# PART1.net
KiCad netlist of a schematic drawn in Altium Designer
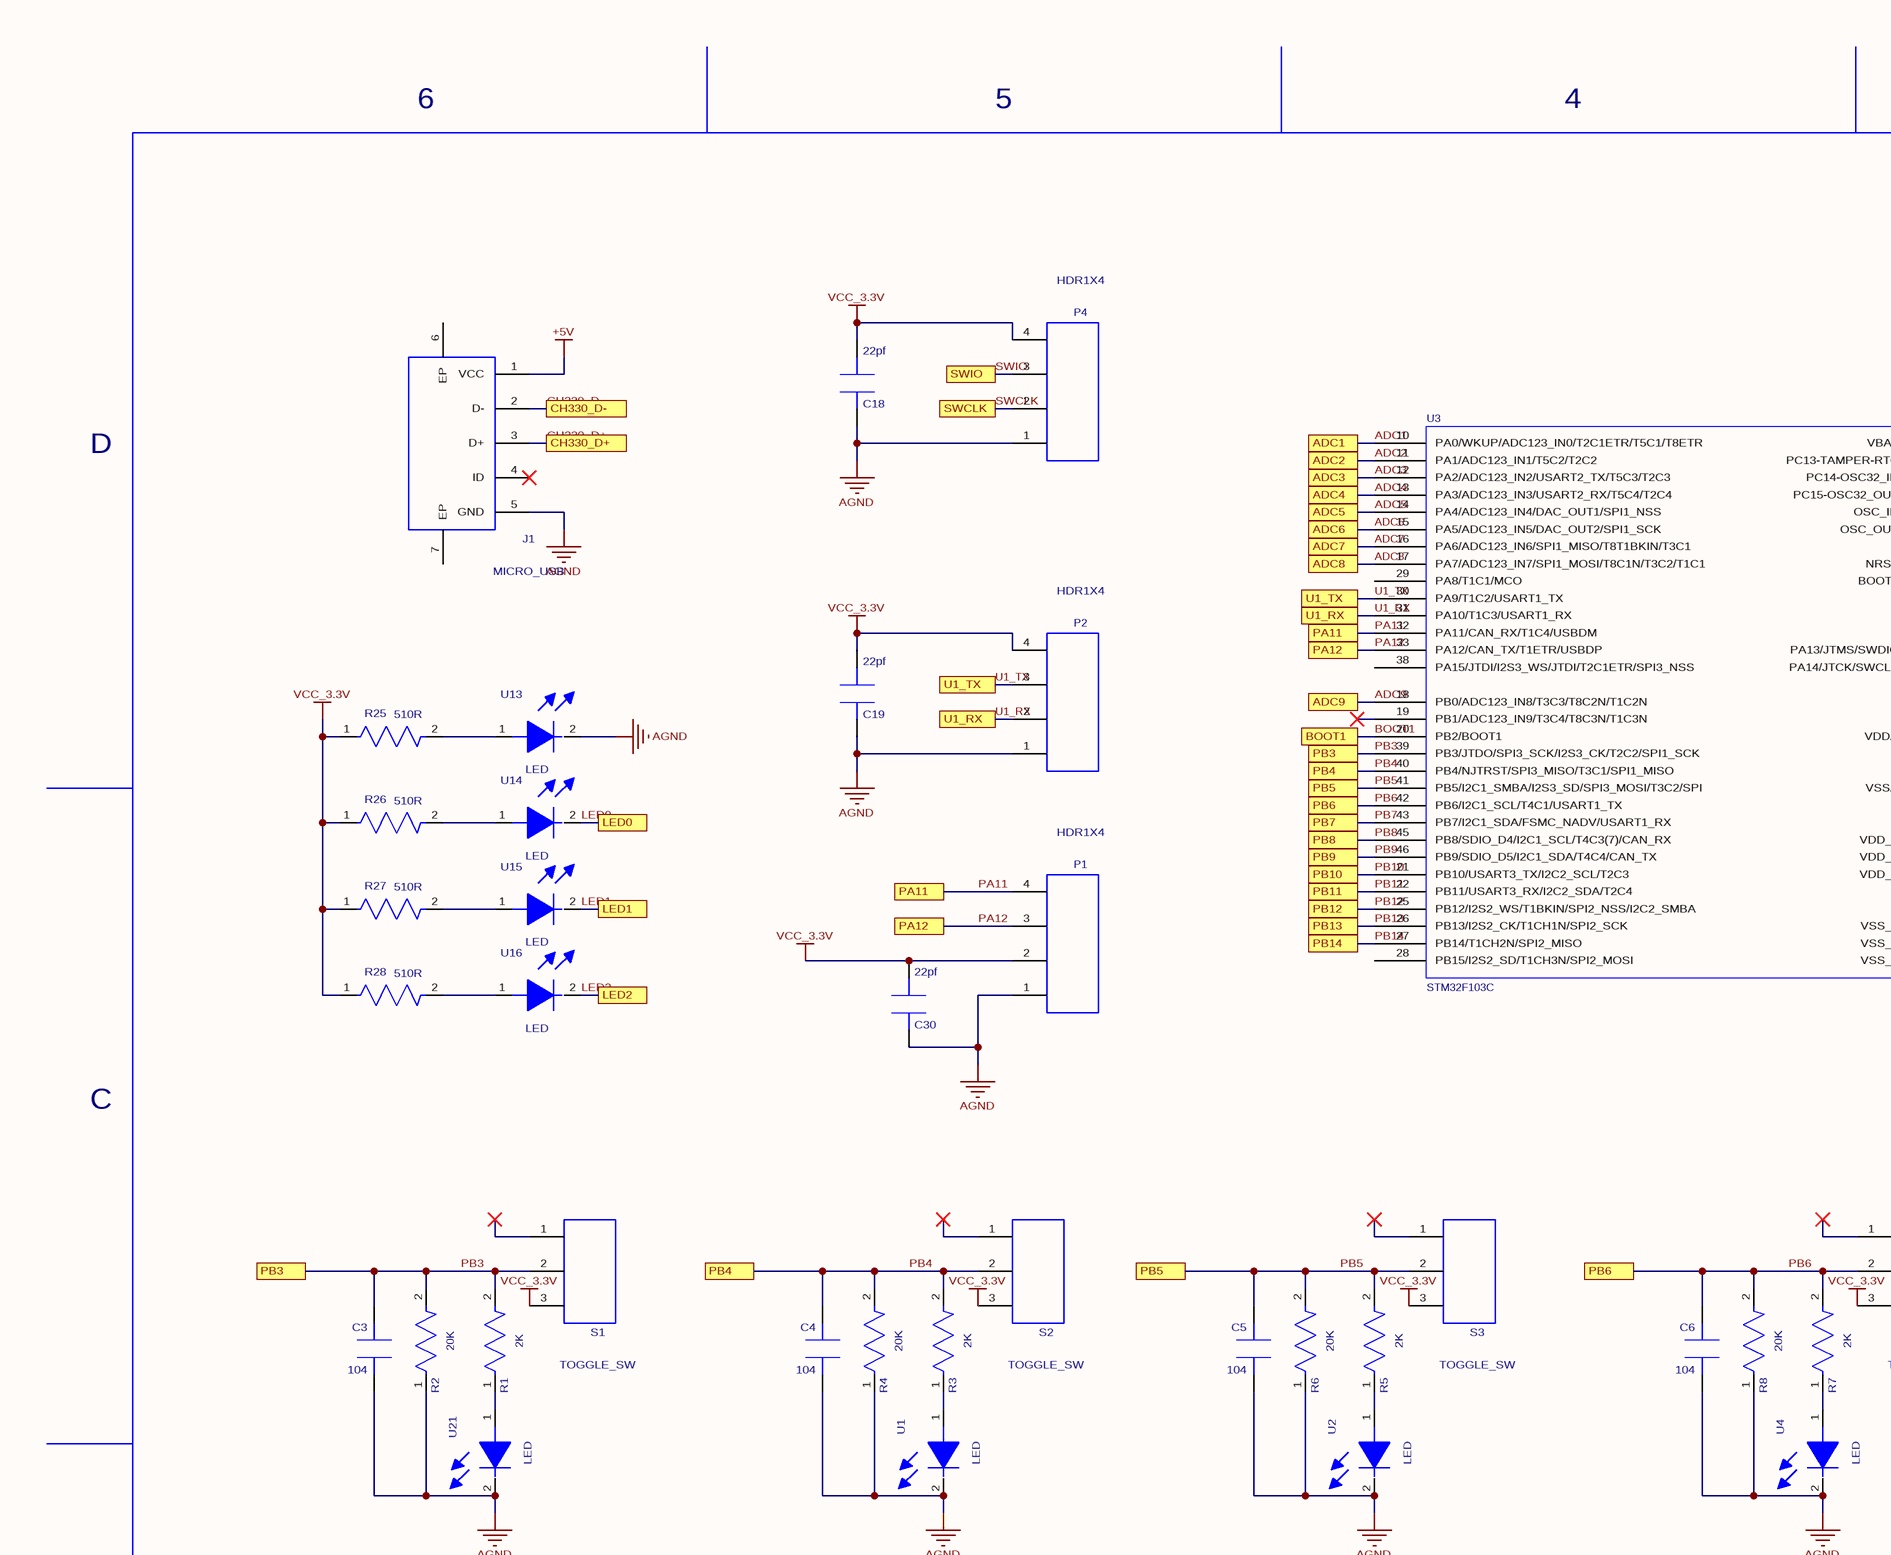
[diagram p0: PART1.SchDoc, top left]
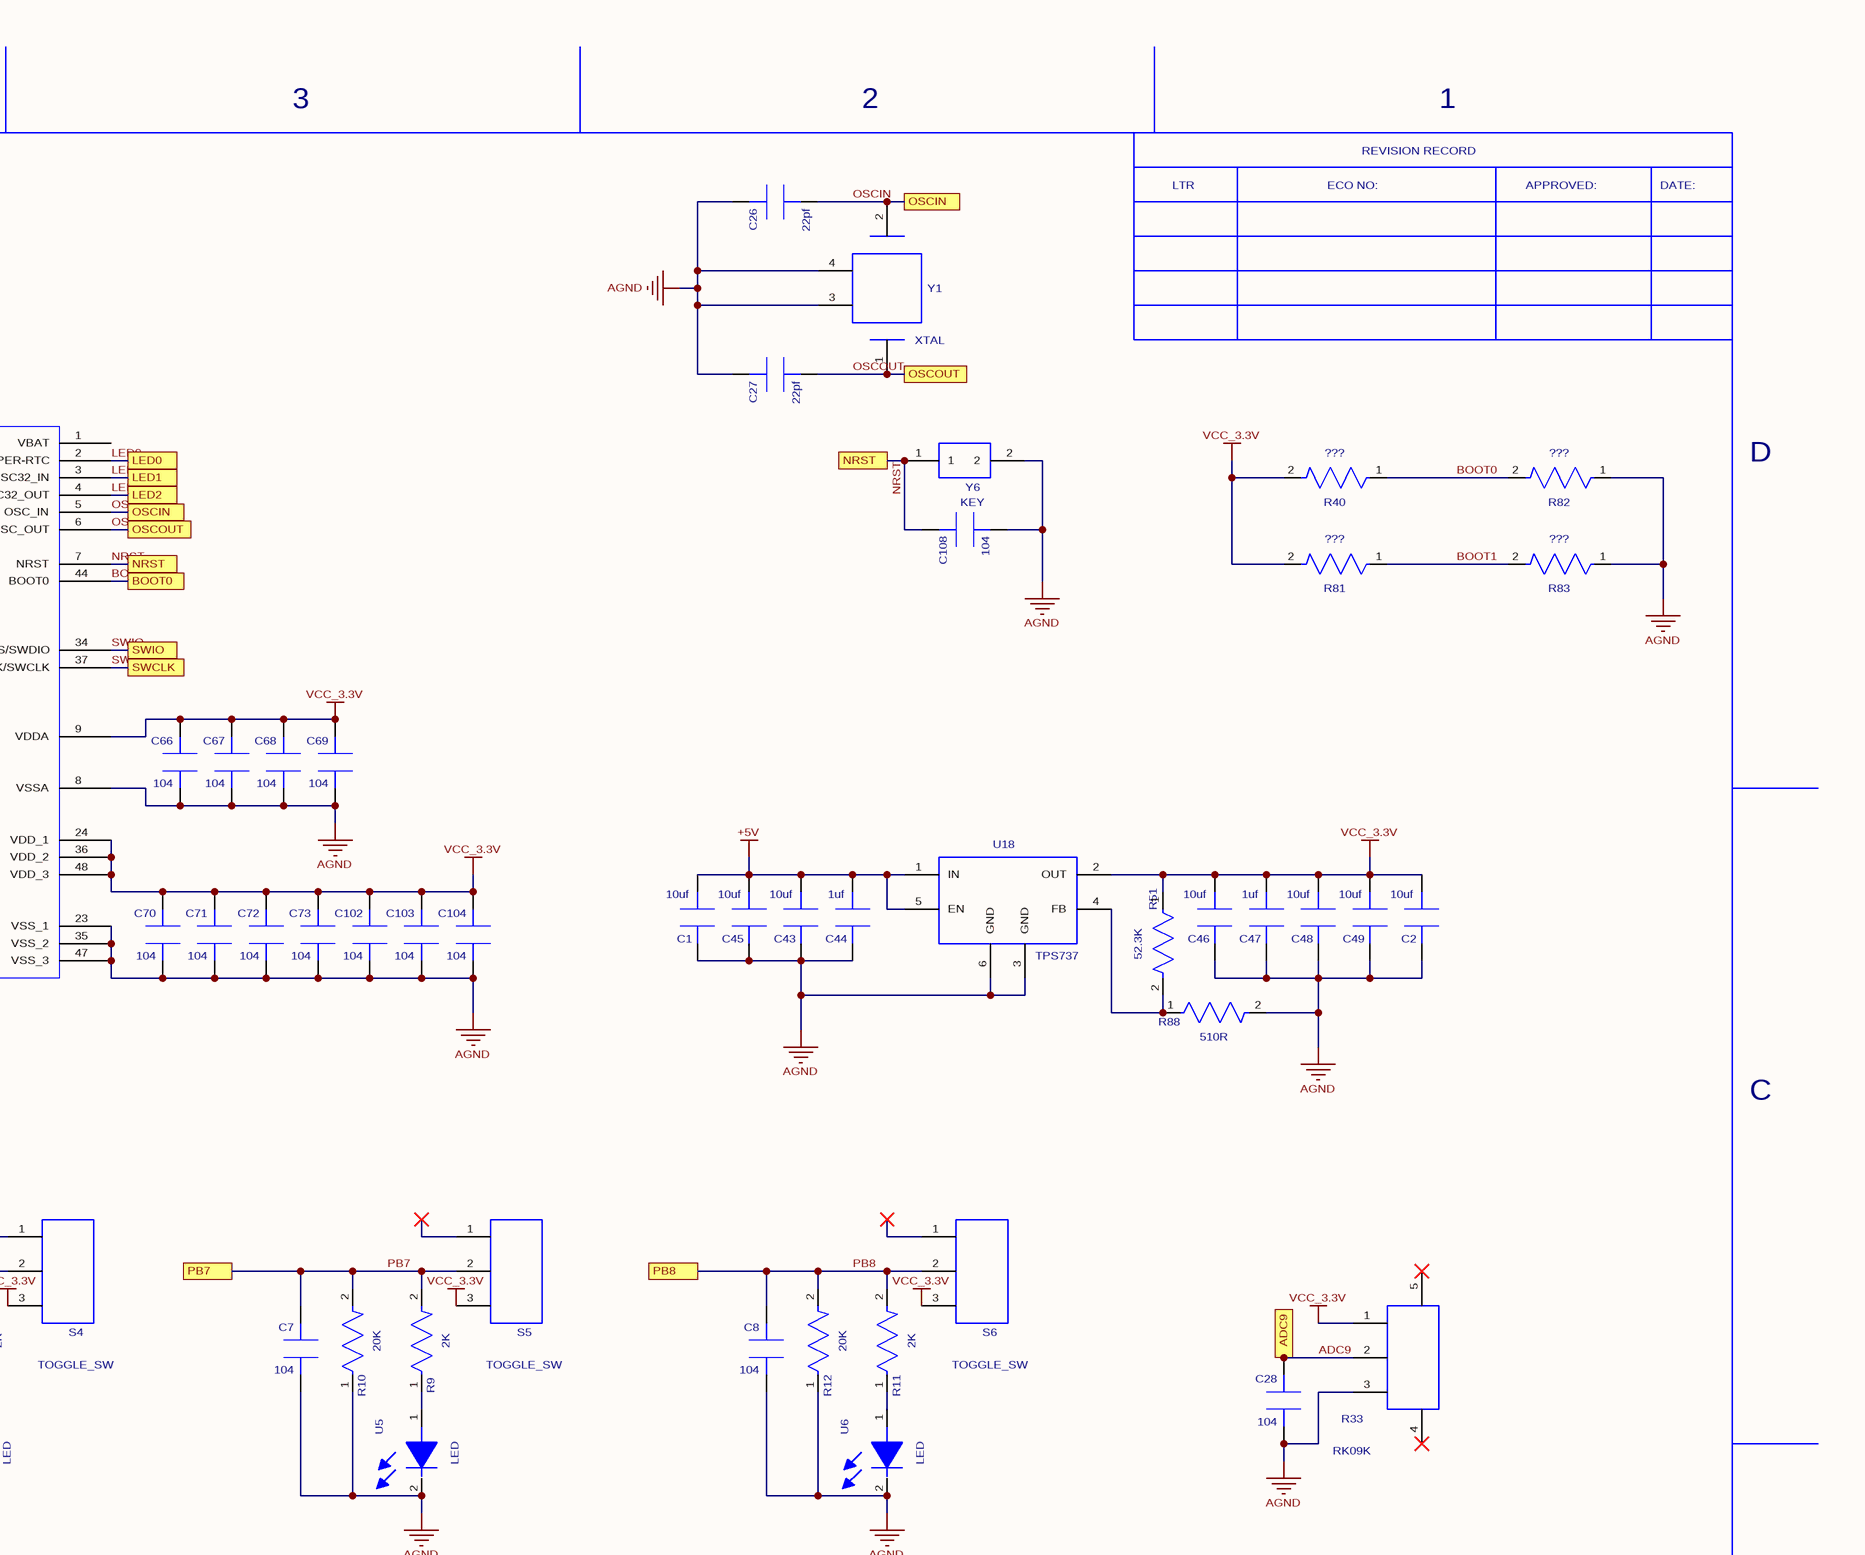
[diagram p1: PART1.SchDoc, top right]
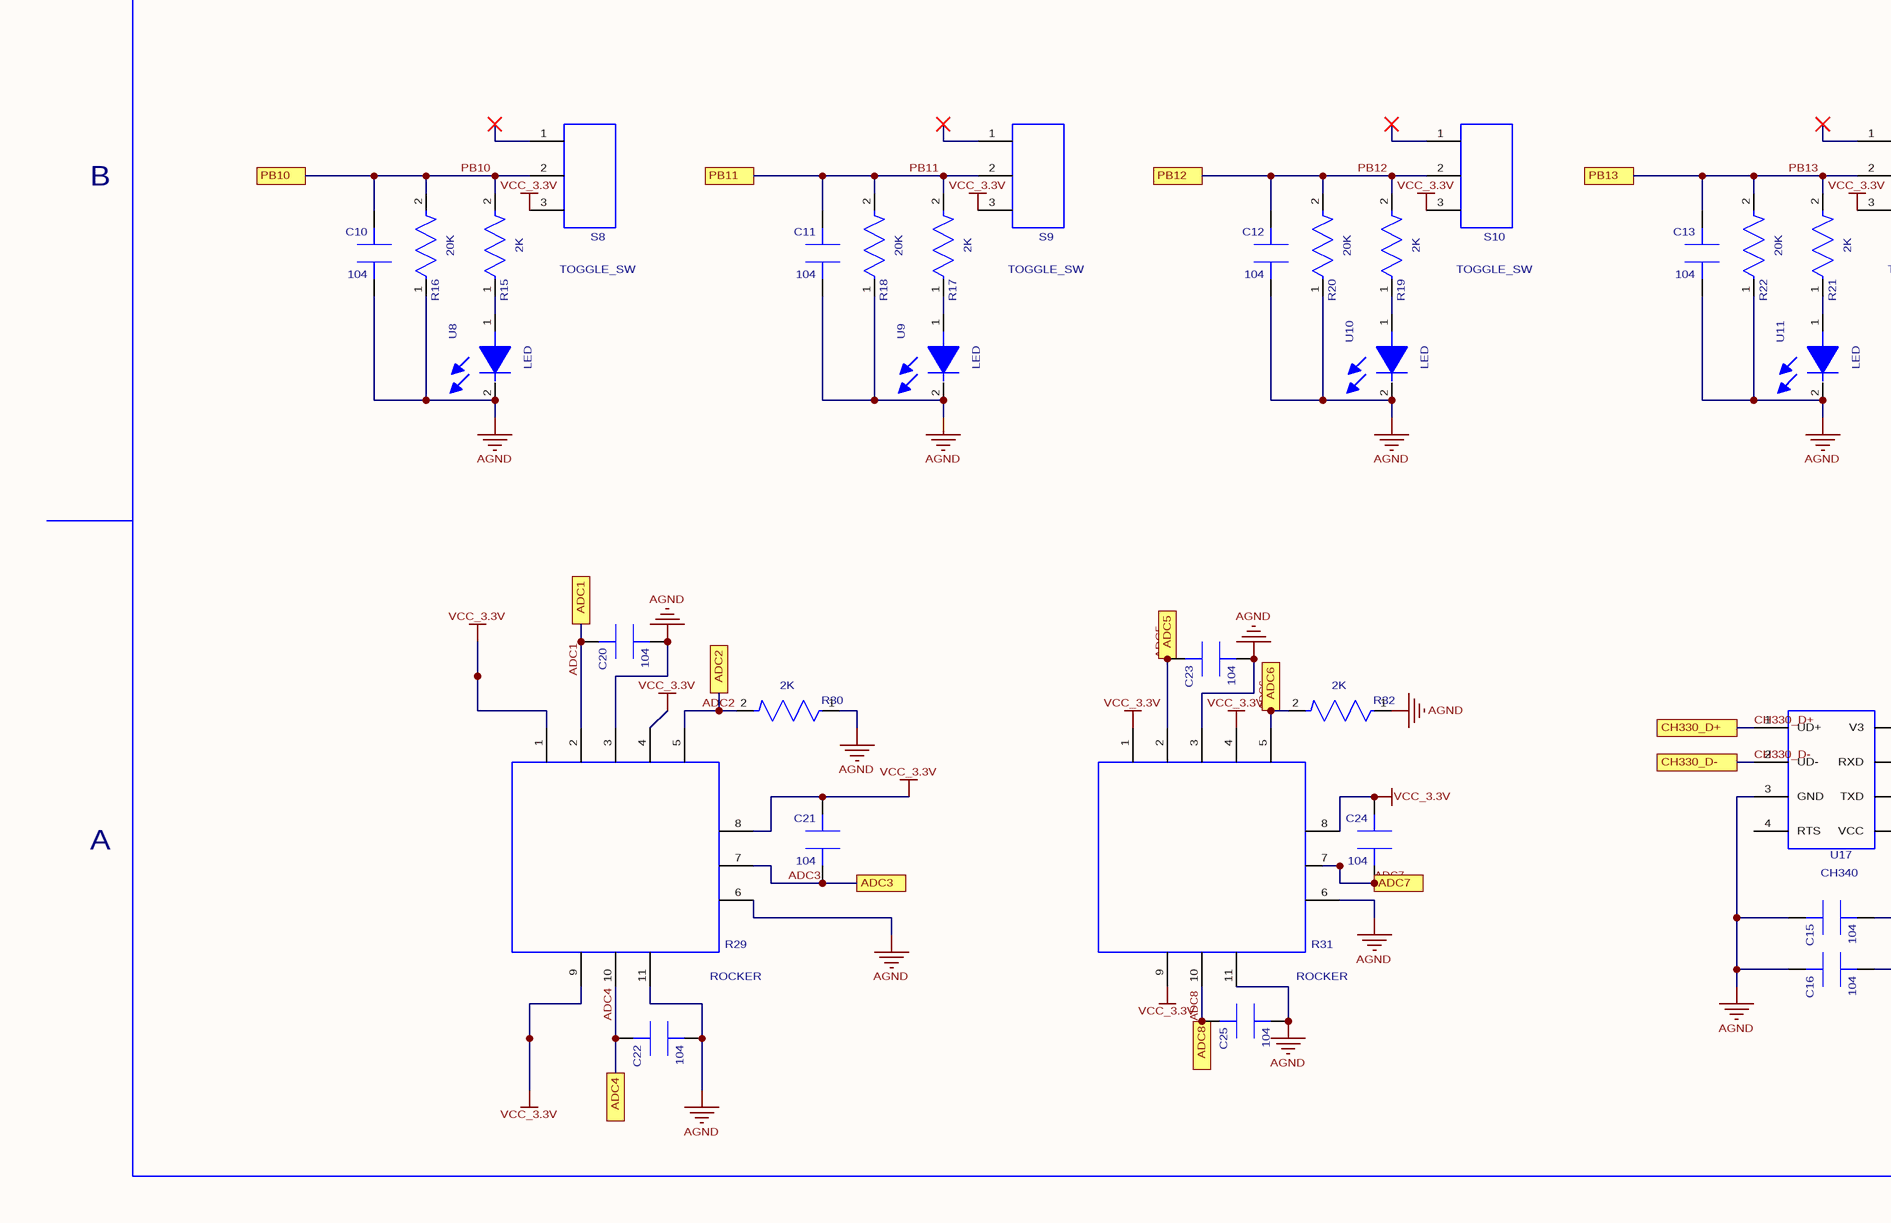
[diagram p2: PART1.SchDoc, bottom left]
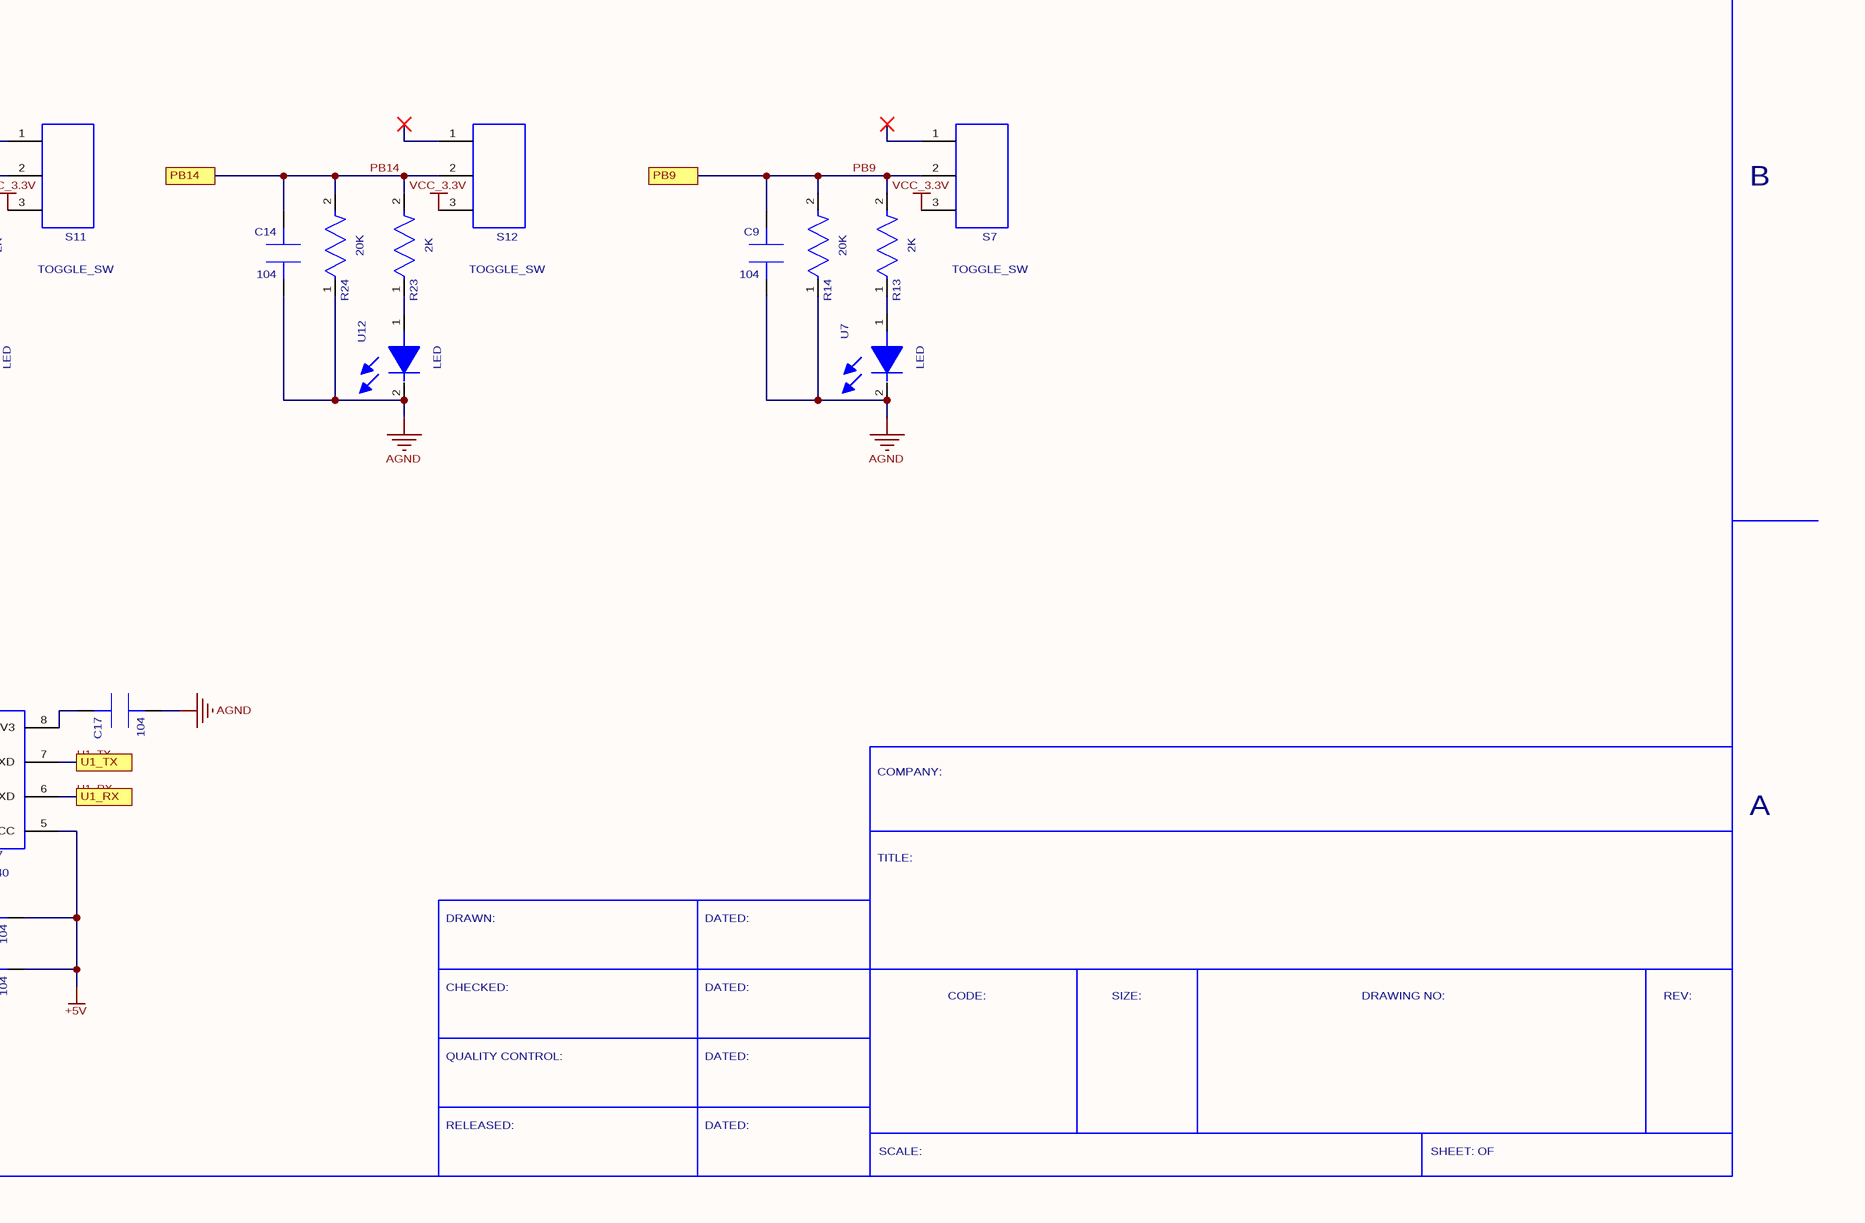
[diagram p3: PART1.SchDoc, bottom right]

(export (version "E")
  (design (tool "Eeschema 10.0.6"))
  (components
    (comp (ref "C1")
      (value "10uf")
      (footprint "1206C")
      (description "RADIAL FILM CAPACITOR, MIL-SPEC SIZE CFR04R SIZE 'C'")
      (fields (field (name "TOLERANCE") "???") (field (name "PART NUMBER") "TBD"))
      (libsource (lib "*") (part "CAP-CFR04R-C"))
    )
    (comp (ref "C2")
      (value "10uf")
      (footprint "1206C")
      (description "RADIAL FILM CAPACITOR, MIL-SPEC SIZE CFR04R SIZE 'C'")
      (fields (field (name "TOLERANCE") "???") (field (name "PART NUMBER") "TBD"))
      (libsource (lib "*") (part "CAP-CFR04R-C"))
    )
    (comp (ref "C3")
      (value "104")
      (footprint "0603C")
      (description "RADIAL FILM CAPACITOR, MIL-SPEC SIZE CFR04R SIZE 'C'")
      (fields (field (name "TOLERANCE") "???") (field (name "PART NUMBER") "TBD"))
      (libsource (lib "*") (part "CAP-CFR04R-C"))
    )
    (comp (ref "C4")
      (value "104")
      (footprint "0603C")
      (description "RADIAL FILM CAPACITOR, MIL-SPEC SIZE CFR04R SIZE 'C'")
      (fields (field (name "TOLERANCE") "???") (field (name "PART NUMBER") "TBD"))
      (libsource (lib "*") (part "CAP-CFR04R-C"))
    )
    (comp (ref "C5")
      (value "104")
      (footprint "0603C")
      (description "RADIAL FILM CAPACITOR, MIL-SPEC SIZE CFR04R SIZE 'C'")
      (fields (field (name "TOLERANCE") "???") (field (name "PART NUMBER") "TBD"))
      (libsource (lib "*") (part "CAP-CFR04R-C"))
    )
    (comp (ref "C6")
      (value "104")
      (footprint "0603C")
      (description "RADIAL FILM CAPACITOR, MIL-SPEC SIZE CFR04R SIZE 'C'")
      (fields (field (name "TOLERANCE") "???") (field (name "PART NUMBER") "TBD"))
      (libsource (lib "*") (part "CAP-CFR04R-C"))
    )
    (comp (ref "C7")
      (value "104")
      (footprint "0603C")
      (description "RADIAL FILM CAPACITOR, MIL-SPEC SIZE CFR04R SIZE 'C'")
      (fields (field (name "TOLERANCE") "???") (field (name "PART NUMBER") "TBD"))
      (libsource (lib "*") (part "CAP-CFR04R-C"))
    )
    (comp (ref "C8")
      (value "104")
      (footprint "0603C")
      (description "RADIAL FILM CAPACITOR, MIL-SPEC SIZE CFR04R SIZE 'C'")
      (fields (field (name "TOLERANCE") "???") (field (name "PART NUMBER") "TBD"))
      (libsource (lib "*") (part "CAP-CFR04R-C"))
    )
    (comp (ref "C9")
      (value "104")
      (footprint "0603C")
      (description "RADIAL FILM CAPACITOR, MIL-SPEC SIZE CFR04R SIZE 'C'")
      (fields (field (name "TOLERANCE") "???") (field (name "PART NUMBER") "TBD"))
      (libsource (lib "*") (part "CAP-CFR04R-C"))
    )
    (comp (ref "C10")
      (value "104")
      (footprint "0603C")
      (description "RADIAL FILM CAPACITOR, MIL-SPEC SIZE CFR04R SIZE 'C'")
      (fields (field (name "TOLERANCE") "???") (field (name "PART NUMBER") "TBD"))
      (libsource (lib "*") (part "CAP-CFR04R-C"))
    )
    (comp (ref "C11")
      (value "104")
      (footprint "0603C")
      (description "RADIAL FILM CAPACITOR, MIL-SPEC SIZE CFR04R SIZE 'C'")
      (fields (field (name "TOLERANCE") "???") (field (name "PART NUMBER") "TBD"))
      (libsource (lib "*") (part "CAP-CFR04R-C"))
    )
    (comp (ref "C12")
      (value "104")
      (footprint "0603C")
      (description "RADIAL FILM CAPACITOR, MIL-SPEC SIZE CFR04R SIZE 'C'")
      (fields (field (name "TOLERANCE") "???") (field (name "PART NUMBER") "TBD"))
      (libsource (lib "*") (part "CAP-CFR04R-C"))
    )
    (comp (ref "C13")
      (value "104")
      (footprint "0603C")
      (description "RADIAL FILM CAPACITOR, MIL-SPEC SIZE CFR04R SIZE 'C'")
      (fields (field (name "TOLERANCE") "???") (field (name "PART NUMBER") "TBD"))
      (libsource (lib "*") (part "CAP-CFR04R-C"))
    )
    (comp (ref "C14")
      (value "104")
      (footprint "0603C")
      (description "RADIAL FILM CAPACITOR, MIL-SPEC SIZE CFR04R SIZE 'C'")
      (fields (field (name "TOLERANCE") "???") (field (name "PART NUMBER") "TBD"))
      (libsource (lib "*") (part "CAP-CFR04R-C"))
    )
    (comp (ref "C15")
      (value "104")
      (footprint "0603C")
      (description "RADIAL FILM CAPACITOR, MIL-SPEC SIZE CFR04R SIZE 'C'")
      (fields (field (name "TOLERANCE") "???") (field (name "PART NUMBER") "TBD"))
      (libsource (lib "*") (part "CAP-CFR04R-C"))
    )
    (comp (ref "C16")
      (value "104")
      (footprint "0805C")
      (description "RADIAL FILM CAPACITOR, MIL-SPEC SIZE CFR04R SIZE 'C'")
      (fields (field (name "TOLERANCE") "???") (field (name "PART NUMBER") "TBD"))
      (libsource (lib "*") (part "CAP-CFR04R-C"))
    )
    (comp (ref "C17")
      (value "104")
      (footprint "0603C")
      (description "RADIAL FILM CAPACITOR, MIL-SPEC SIZE CFR04R SIZE 'C'")
      (fields (field (name "TOLERANCE") "???") (field (name "PART NUMBER") "TBD"))
      (libsource (lib "*") (part "CAP-CFR04R-C"))
    )
    (comp (ref "C18")
      (value "22pf")
      (footprint "0603C")
      (description "RADIAL FILM CAPACITOR, MIL-SPEC SIZE CFR04R SIZE 'C'")
      (fields (field (name "TOLERANCE") "???") (field (name "PART NUMBER") "TBD"))
      (libsource (lib "*") (part "CAP-CFR04R-C"))
    )
    (comp (ref "C19")
      (value "22pf")
      (footprint "0603C")
      (description "RADIAL FILM CAPACITOR, MIL-SPEC SIZE CFR04R SIZE 'C'")
      (fields (field (name "TOLERANCE") "???") (field (name "PART NUMBER") "TBD"))
      (libsource (lib "*") (part "CAP-CFR04R-C"))
    )
    (comp (ref "C20")
      (value "104")
      (footprint "0805C")
      (description "RADIAL FILM CAPACITOR, MIL-SPEC SIZE CFR04R SIZE 'C'")
      (fields (field (name "TOLERANCE") "???") (field (name "PART NUMBER") "TBD"))
      (libsource (lib "*") (part "CAP-CFR04R-C"))
    )
    (comp (ref "C21")
      (value "104")
      (footprint "0805C")
      (description "RADIAL FILM CAPACITOR, MIL-SPEC SIZE CFR04R SIZE 'C'")
      (fields (field (name "TOLERANCE") "???") (field (name "PART NUMBER") "TBD"))
      (libsource (lib "*") (part "CAP-CFR04R-C"))
    )
    (comp (ref "C22")
      (value "104")
      (footprint "0805C")
      (description "RADIAL FILM CAPACITOR, MIL-SPEC SIZE CFR04R SIZE 'C'")
      (fields (field (name "TOLERANCE") "???") (field (name "PART NUMBER") "TBD"))
      (libsource (lib "*") (part "CAP-CFR04R-C"))
    )
    (comp (ref "C23")
      (value "104")
      (footprint "0805C")
      (description "RADIAL FILM CAPACITOR, MIL-SPEC SIZE CFR04R SIZE 'C'")
      (fields (field (name "TOLERANCE") "???") (field (name "PART NUMBER") "TBD"))
      (libsource (lib "*") (part "CAP-CFR04R-C"))
    )
    (comp (ref "C24")
      (value "104")
      (footprint "0805C")
      (description "RADIAL FILM CAPACITOR, MIL-SPEC SIZE CFR04R SIZE 'C'")
      (fields (field (name "TOLERANCE") "???") (field (name "PART NUMBER") "TBD"))
      (libsource (lib "*") (part "CAP-CFR04R-C"))
    )
    (comp (ref "C25")
      (value "104")
      (footprint "0805C")
      (description "RADIAL FILM CAPACITOR, MIL-SPEC SIZE CFR04R SIZE 'C'")
      (fields (field (name "TOLERANCE") "???") (field (name "PART NUMBER") "TBD"))
      (libsource (lib "*") (part "CAP-CFR04R-C"))
    )
    (comp (ref "C26")
      (value "22pf")
      (footprint "0603C")
      (description "RADIAL FILM CAPACITOR, MIL-SPEC SIZE CFR04R SIZE 'C'")
      (fields (field (name "TOLERANCE") "???") (field (name "PART NUMBER") "TBD"))
      (libsource (lib "*") (part "CAP-CFR04R-C"))
    )
    (comp (ref "C27")
      (value "22pf")
      (footprint "0603C")
      (description "RADIAL FILM CAPACITOR, MIL-SPEC SIZE CFR04R SIZE 'C'")
      (fields (field (name "TOLERANCE") "???") (field (name "PART NUMBER") "TBD"))
      (libsource (lib "*") (part "CAP-CFR04R-C"))
    )
    (comp (ref "C28")
      (value "104")
      (footprint "0603C")
      (description "RADIAL FILM CAPACITOR, MIL-SPEC SIZE CFR04R SIZE 'C'")
      (fields (field (name "TOLERANCE") "???") (field (name "PART NUMBER") "TBD"))
      (libsource (lib "*") (part "CAP-CFR04R-C"))
    )
    (comp (ref "C30")
      (value "22pf")
      (footprint "0603C")
      (description "RADIAL FILM CAPACITOR, MIL-SPEC SIZE CFR04R SIZE 'C'")
      (fields (field (name "TOLERANCE") "???") (field (name "PART NUMBER") "TBD"))
      (libsource (lib "*") (part "CAP-CFR04R-C"))
    )
    (comp (ref "C43")
      (value "10uf")
      (footprint "1206C")
      (description "RADIAL FILM CAPACITOR, MIL-SPEC SIZE CFR04R SIZE 'C'")
      (fields (field (name "TOLERANCE") "???") (field (name "PART NUMBER") "TBD"))
      (libsource (lib "*") (part "CAP-CFR04R-C"))
    )
    (comp (ref "C44")
      (value "1uf")
      (footprint "0805C")
      (description "RADIAL FILM CAPACITOR, MIL-SPEC SIZE CFR04R SIZE 'C'")
      (fields (field (name "TOLERANCE") "???") (field (name "PART NUMBER") "TBD"))
      (libsource (lib "*") (part "CAP-CFR04R-C"))
    )
    (comp (ref "C45")
      (value "10uf")
      (footprint "1206C")
      (description "RADIAL FILM CAPACITOR, MIL-SPEC SIZE CFR04R SIZE 'C'")
      (fields (field (name "TOLERANCE") "???") (field (name "PART NUMBER") "TBD"))
      (libsource (lib "*") (part "CAP-CFR04R-C"))
    )
    (comp (ref "C46")
      (value "10uf")
      (footprint "1206C")
      (description "RADIAL FILM CAPACITOR, MIL-SPEC SIZE CFR04R SIZE 'C'")
      (fields (field (name "TOLERANCE") "???") (field (name "PART NUMBER") "TBD"))
      (libsource (lib "*") (part "CAP-CFR04R-C"))
    )
    (comp (ref "C47")
      (value "1uf")
      (footprint "0805C")
      (description "RADIAL FILM CAPACITOR, MIL-SPEC SIZE CFR04R SIZE 'C'")
      (fields (field (name "TOLERANCE") "???") (field (name "PART NUMBER") "TBD"))
      (libsource (lib "*") (part "CAP-CFR04R-C"))
    )
    (comp (ref "C48")
      (value "10uf")
      (footprint "1206C")
      (description "RADIAL FILM CAPACITOR, MIL-SPEC SIZE CFR04R SIZE 'C'")
      (fields (field (name "TOLERANCE") "???") (field (name "PART NUMBER") "TBD"))
      (libsource (lib "*") (part "CAP-CFR04R-C"))
    )
    (comp (ref "C49")
      (value "10uf")
      (footprint "1206C")
      (description "RADIAL FILM CAPACITOR, MIL-SPEC SIZE CFR04R SIZE 'C'")
      (fields (field (name "TOLERANCE") "???") (field (name "PART NUMBER") "TBD"))
      (libsource (lib "*") (part "CAP-CFR04R-C"))
    )
    (comp (ref "C66")
      (value "104")
      (footprint "0805C")
      (description "RADIAL FILM CAPACITOR, MIL-SPEC SIZE CFR04R SIZE 'C'")
      (fields (field (name "TOLERANCE") "???") (field (name "PART NUMBER") "TBD"))
      (libsource (lib "*") (part "CAP-CFR04R-C"))
    )
    (comp (ref "C67")
      (value "104")
      (footprint "0805C")
      (description "RADIAL FILM CAPACITOR, MIL-SPEC SIZE CFR04R SIZE 'C'")
      (fields (field (name "TOLERANCE") "???") (field (name "PART NUMBER") "TBD"))
      (libsource (lib "*") (part "CAP-CFR04R-C"))
    )
    (comp (ref "C68")
      (value "104")
      (footprint "0805C")
      (description "RADIAL FILM CAPACITOR, MIL-SPEC SIZE CFR04R SIZE 'C'")
      (fields (field (name "TOLERANCE") "???") (field (name "PART NUMBER") "TBD"))
      (libsource (lib "*") (part "CAP-CFR04R-C"))
    )
    (comp (ref "C69")
      (value "104")
      (footprint "0805C")
      (description "RADIAL FILM CAPACITOR, MIL-SPEC SIZE CFR04R SIZE 'C'")
      (fields (field (name "TOLERANCE") "???") (field (name "PART NUMBER") "TBD"))
      (libsource (lib "*") (part "CAP-CFR04R-C"))
    )
    (comp (ref "C70")
      (value "104")
      (footprint "0805C")
      (description "RADIAL FILM CAPACITOR, MIL-SPEC SIZE CFR04R SIZE 'C'")
      (fields (field (name "TOLERANCE") "???") (field (name "PART NUMBER") "TBD"))
      (libsource (lib "*") (part "CAP-CFR04R-C"))
    )
    (comp (ref "C71")
      (value "104")
      (footprint "0805C")
      (description "RADIAL FILM CAPACITOR, MIL-SPEC SIZE CFR04R SIZE 'C'")
      (fields (field (name "TOLERANCE") "???") (field (name "PART NUMBER") "TBD"))
      (libsource (lib "*") (part "CAP-CFR04R-C"))
    )
    (comp (ref "C72")
      (value "104")
      (footprint "0805C")
      (description "RADIAL FILM CAPACITOR, MIL-SPEC SIZE CFR04R SIZE 'C'")
      (fields (field (name "TOLERANCE") "???") (field (name "PART NUMBER") "TBD"))
      (libsource (lib "*") (part "CAP-CFR04R-C"))
    )
    (comp (ref "C73")
      (value "104")
      (footprint "0805C")
      (description "RADIAL FILM CAPACITOR, MIL-SPEC SIZE CFR04R SIZE 'C'")
      (fields (field (name "TOLERANCE") "???") (field (name "PART NUMBER") "TBD"))
      (libsource (lib "*") (part "CAP-CFR04R-C"))
    )
    (comp (ref "C102")
      (value "104")
      (footprint "0805C")
      (description "RADIAL FILM CAPACITOR, MIL-SPEC SIZE CFR04R SIZE 'C'")
      (fields (field (name "TOLERANCE") "???") (field (name "PART NUMBER") "TBD"))
      (libsource (lib "*") (part "CAP-CFR04R-C"))
    )
    (comp (ref "C103")
      (value "104")
      (footprint "0805C")
      (description "RADIAL FILM CAPACITOR, MIL-SPEC SIZE CFR04R SIZE 'C'")
      (fields (field (name "TOLERANCE") "???") (field (name "PART NUMBER") "TBD"))
      (libsource (lib "*") (part "CAP-CFR04R-C"))
    )
    (comp (ref "C104")
      (value "104")
      (footprint "0805C")
      (description "RADIAL FILM CAPACITOR, MIL-SPEC SIZE CFR04R SIZE 'C'")
      (fields (field (name "TOLERANCE") "???") (field (name "PART NUMBER") "TBD"))
      (libsource (lib "*") (part "CAP-CFR04R-C"))
    )
    (comp (ref "C108")
      (value "104")
      (footprint "0805C")
      (description "RADIAL FILM CAPACITOR, MIL-SPEC SIZE CFR04R SIZE 'C'")
      (fields (field (name "TOLERANCE") "???") (field (name "PART NUMBER") "TBD"))
      (libsource (lib "*") (part "CAP-CFR04R-C"))
    )
    (comp (ref "J1") (value "MICRO_USB") (footprint "MICRO_USB") (libsource (lib "*") (part "MICRO_USB")))
    (comp (ref "P1") (value "HDR1X4") (footprint "HDR1X4(2)") (libsource (lib "*") (part "HDR1X4")))
    (comp (ref "P2") (value "HDR1X4") (footprint "HDR1X4(2)") (libsource (lib "*") (part "HDR1X4")))
    (comp (ref "P4") (value "HDR1X4") (footprint "HDR1X4(2)") (libsource (lib "*") (part "HDR1X4")))
    (comp (ref "R1")
      (value "2K")
      (footprint "0603R")
      (description "WIRE WOUND RESISTOR 3.4 X 7.05 MM")
      (fields (field (name "Comment") "RES-WR1"))
      (libsource (lib "*") (part "RES-WR1"))
    )
    (comp (ref "R2")
      (value "20K")
      (footprint "0603R")
      (description "WIRE WOUND RESISTOR 3.4 X 7.05 MM")
      (fields (field (name "Comment") "RES-WR1"))
      (libsource (lib "*") (part "RES-WR1"))
    )
    (comp (ref "R3")
      (value "2K")
      (footprint "0603R")
      (description "WIRE WOUND RESISTOR 3.4 X 7.05 MM")
      (fields (field (name "Comment") "RES-WR1"))
      (libsource (lib "*") (part "RES-WR1"))
    )
    (comp (ref "R4")
      (value "20K")
      (footprint "0603R")
      (description "WIRE WOUND RESISTOR 3.4 X 7.05 MM")
      (fields (field (name "Comment") "RES-WR1"))
      (libsource (lib "*") (part "RES-WR1"))
    )
    (comp (ref "R5")
      (value "2K")
      (footprint "0603R")
      (description "WIRE WOUND RESISTOR 3.4 X 7.05 MM")
      (fields (field (name "Comment") "RES-WR1"))
      (libsource (lib "*") (part "RES-WR1"))
    )
    (comp (ref "R6")
      (value "20K")
      (footprint "0603R")
      (description "WIRE WOUND RESISTOR 3.4 X 7.05 MM")
      (fields (field (name "Comment") "RES-WR1"))
      (libsource (lib "*") (part "RES-WR1"))
    )
    (comp (ref "R7")
      (value "2K")
      (footprint "0603R")
      (description "WIRE WOUND RESISTOR 3.4 X 7.05 MM")
      (fields (field (name "Comment") "RES-WR1"))
      (libsource (lib "*") (part "RES-WR1"))
    )
    (comp (ref "R8")
      (value "20K")
      (footprint "0603R")
      (description "WIRE WOUND RESISTOR 3.4 X 7.05 MM")
      (fields (field (name "Comment") "RES-WR1"))
      (libsource (lib "*") (part "RES-WR1"))
    )
    (comp (ref "R9")
      (value "2K")
      (footprint "0603R")
      (description "WIRE WOUND RESISTOR 3.4 X 7.05 MM")
      (fields (field (name "Comment") "RES-WR1"))
      (libsource (lib "*") (part "RES-WR1"))
    )
    (comp (ref "R10")
      (value "20K")
      (footprint "0603R")
      (description "WIRE WOUND RESISTOR 3.4 X 7.05 MM")
      (fields (field (name "Comment") "RES-WR1"))
      (libsource (lib "*") (part "RES-WR1"))
    )
    (comp (ref "R11")
      (value "2K")
      (footprint "0603R")
      (description "WIRE WOUND RESISTOR 3.4 X 7.05 MM")
      (fields (field (name "Comment") "RES-WR1"))
      (libsource (lib "*") (part "RES-WR1"))
    )
    (comp (ref "R12")
      (value "20K")
      (footprint "0603R")
      (description "WIRE WOUND RESISTOR 3.4 X 7.05 MM")
      (fields (field (name "Comment") "RES-WR1"))
      (libsource (lib "*") (part "RES-WR1"))
    )
    (comp (ref "R13")
      (value "2K")
      (footprint "0603R")
      (description "WIRE WOUND RESISTOR 3.4 X 7.05 MM")
      (fields (field (name "Comment") "RES-WR1"))
      (libsource (lib "*") (part "RES-WR1"))
    )
    (comp (ref "R14")
      (value "20K")
      (footprint "0603R")
      (description "WIRE WOUND RESISTOR 3.4 X 7.05 MM")
      (fields (field (name "Comment") "RES-WR1"))
      (libsource (lib "*") (part "RES-WR1"))
    )
    (comp (ref "R15")
      (value "2K")
      (footprint "0603R")
      (description "WIRE WOUND RESISTOR 3.4 X 7.05 MM")
      (fields (field (name "Comment") "RES-WR1"))
      (libsource (lib "*") (part "RES-WR1"))
    )
    (comp (ref "R16")
      (value "20K")
      (footprint "0603R")
      (description "WIRE WOUND RESISTOR 3.4 X 7.05 MM")
      (fields (field (name "Comment") "RES-WR1"))
      (libsource (lib "*") (part "RES-WR1"))
    )
    (comp (ref "R17")
      (value "2K")
      (footprint "0603R")
      (description "WIRE WOUND RESISTOR 3.4 X 7.05 MM")
      (fields (field (name "Comment") "RES-WR1"))
      (libsource (lib "*") (part "RES-WR1"))
    )
    (comp (ref "R18")
      (value "20K")
      (footprint "0603R")
      (description "WIRE WOUND RESISTOR 3.4 X 7.05 MM")
      (fields (field (name "Comment") "RES-WR1"))
      (libsource (lib "*") (part "RES-WR1"))
    )
    (comp (ref "R19")
      (value "2K")
      (footprint "0603R")
      (description "WIRE WOUND RESISTOR 3.4 X 7.05 MM")
      (fields (field (name "Comment") "RES-WR1"))
      (libsource (lib "*") (part "RES-WR1"))
    )
    (comp (ref "R20")
      (value "20K")
      (footprint "0603R")
      (description "WIRE WOUND RESISTOR 3.4 X 7.05 MM")
      (fields (field (name "Comment") "RES-WR1"))
      (libsource (lib "*") (part "RES-WR1"))
    )
    (comp (ref "R21")
      (value "2K")
      (footprint "0603R")
      (description "WIRE WOUND RESISTOR 3.4 X 7.05 MM")
      (fields (field (name "Comment") "RES-WR1"))
      (libsource (lib "*") (part "RES-WR1"))
    )
    (comp (ref "R22")
      (value "20K")
      (footprint "0603R")
      (description "WIRE WOUND RESISTOR 3.4 X 7.05 MM")
      (fields (field (name "Comment") "RES-WR1"))
      (libsource (lib "*") (part "RES-WR1"))
    )
    (comp (ref "R23")
      (value "2K")
      (footprint "0603R")
      (description "WIRE WOUND RESISTOR 3.4 X 7.05 MM")
      (fields (field (name "Comment") "RES-WR1"))
      (libsource (lib "*") (part "RES-WR1"))
    )
    (comp (ref "R24")
      (value "20K")
      (footprint "0603R")
      (description "WIRE WOUND RESISTOR 3.4 X 7.05 MM")
      (fields (field (name "Comment") "RES-WR1"))
      (libsource (lib "*") (part "RES-WR1"))
    )
    (comp (ref "R25")
      (value "510R")
      (footprint "0603R")
      (description "WIRE WOUND RESISTOR 3.4 X 7.05 MM")
      (fields (field (name "Comment") "RES-WR1"))
      (libsource (lib "*") (part "RES-WR1"))
    )
    (comp (ref "R26")
      (value "510R")
      (footprint "0603R")
      (description "WIRE WOUND RESISTOR 3.4 X 7.05 MM")
      (fields (field (name "Comment") "RES-WR1"))
      (libsource (lib "*") (part "RES-WR1"))
    )
    (comp (ref "R27")
      (value "510R")
      (footprint "0603R")
      (description "WIRE WOUND RESISTOR 3.4 X 7.05 MM")
      (fields (field (name "Comment") "RES-WR1"))
      (libsource (lib "*") (part "RES-WR1"))
    )
    (comp (ref "R28")
      (value "510R")
      (footprint "0603R")
      (description "WIRE WOUND RESISTOR 3.4 X 7.05 MM")
      (fields (field (name "Comment") "RES-WR1"))
      (libsource (lib "*") (part "RES-WR1"))
    )
    (comp (ref "R29") (value "ROCKER") (footprint "ROCKER") (libsource (lib "*") (part "ROCKER")))
    (comp (ref "R30")
      (value "2K")
      (footprint "0603R")
      (description "WIRE WOUND RESISTOR 3.4 X 7.05 MM")
      (fields (field (name "Comment") "RES-WR1"))
      (libsource (lib "*") (part "RES-WR1"))
    )
    (comp (ref "R31") (value "ROCKER") (footprint "ROCKER") (libsource (lib "*") (part "ROCKER")))
    (comp (ref "R32")
      (value "2K")
      (footprint "0603R")
      (description "WIRE WOUND RESISTOR 3.4 X 7.05 MM")
      (fields (field (name "Comment") "RES-WR1"))
      (libsource (lib "*") (part "RES-WR1"))
    )
    (comp (ref "R33") (value "RK09K") (footprint "RK09K_RES") (libsource (lib "*") (part "RK09K")))
    (comp (ref "R40")
      (value "???")
      (footprint "0603R")
      (description "WIRE WOUND RESISTOR 3.4 X 7.05 MM")
      (fields (field (name "Comment") "RES-WR1"))
      (libsource (lib "*") (part "RES-WR1"))
    )
    (comp (ref "R51")
      (value "52.3K")
      (footprint "0603R")
      (description "WIRE WOUND RESISTOR 3.4 X 7.05 MM")
      (fields (field (name "Comment") "RES-WR1"))
      (libsource (lib "*") (part "RES-WR1"))
    )
    (comp (ref "R81")
      (value "???")
      (footprint "0603R")
      (description "WIRE WOUND RESISTOR 3.4 X 7.05 MM")
      (fields (field (name "Comment") "RES-WR1"))
      (libsource (lib "*") (part "RES-WR1"))
    )
    (comp (ref "R82")
      (value "???")
      (footprint "0603R")
      (description "WIRE WOUND RESISTOR 3.4 X 7.05 MM")
      (fields (field (name "Comment") "RES-WR1"))
      (libsource (lib "*") (part "RES-WR1"))
    )
    (comp (ref "R83")
      (value "???")
      (footprint "0603R")
      (description "WIRE WOUND RESISTOR 3.4 X 7.05 MM")
      (fields (field (name "Comment") "RES-WR1"))
      (libsource (lib "*") (part "RES-WR1"))
    )
    (comp (ref "R88")
      (value "510R")
      (footprint "0603R")
      (description "WIRE WOUND RESISTOR 3.4 X 7.05 MM")
      (fields (field (name "Comment") "RES-WR1"))
      (libsource (lib "*") (part "RES-WR1"))
    )
    (comp (ref "S1") (value "TOGGLE_SW") (footprint "TOGGLE_SWITCH") (libsource (lib "*") (part "TOGGLE_SW")))
    (comp (ref "S2") (value "TOGGLE_SW") (footprint "TOGGLE_SWITCH") (libsource (lib "*") (part "TOGGLE_SW")))
    (comp (ref "S3") (value "TOGGLE_SW") (footprint "TOGGLE_SWITCH") (libsource (lib "*") (part "TOGGLE_SW")))
    (comp (ref "S4") (value "TOGGLE_SW") (footprint "TOGGLE_SWITCH") (libsource (lib "*") (part "TOGGLE_SW")))
    (comp (ref "S5") (value "TOGGLE_SW") (footprint "TOGGLE_SWITCH") (libsource (lib "*") (part "TOGGLE_SW")))
    (comp (ref "S6") (value "TOGGLE_SW") (footprint "TOGGLE_SWITCH") (libsource (lib "*") (part "TOGGLE_SW")))
    (comp (ref "S7") (value "TOGGLE_SW") (footprint "TOGGLE_SWITCH") (libsource (lib "*") (part "TOGGLE_SW")))
    (comp (ref "S8") (value "TOGGLE_SW") (footprint "TOGGLE_SWITCH") (libsource (lib "*") (part "TOGGLE_SW")))
    (comp (ref "S9") (value "TOGGLE_SW") (footprint "TOGGLE_SWITCH") (libsource (lib "*") (part "TOGGLE_SW")))
    (comp (ref "S10")
      (value "TOGGLE_SW")
      (footprint "TOGGLE_SWITCH")
      (libsource (lib "*") (part "TOGGLE_SW"))
    )
    (comp (ref "S11")
      (value "TOGGLE_SW")
      (footprint "TOGGLE_SWITCH")
      (libsource (lib "*") (part "TOGGLE_SW"))
    )
    (comp (ref "S12")
      (value "TOGGLE_SW")
      (footprint "TOGGLE_SWITCH")
      (libsource (lib "*") (part "TOGGLE_SW"))
    )
    (comp (ref "U1")
      (value "DS0")
      (footprint "0805D")
      (fields (field (name "COMMENT_1") "LED"))
      (libsource (lib "*") (part "LED"))
    )
    (comp (ref "U2")
      (value "DS0")
      (footprint "0805D")
      (fields (field (name "COMMENT_1") "LED"))
      (libsource (lib "*") (part "LED"))
    )
    (comp (ref "U3")
      (value "STM32F103C")
      (footprint "LQFP-48_M")
      (description "STM32单片机48引脚")
      (libsource (lib "*") (part "STM32F103C"))
    )
    (comp (ref "U4")
      (value "DS0")
      (footprint "0805D")
      (fields (field (name "COMMENT_1") "LED"))
      (libsource (lib "*") (part "LED"))
    )
    (comp (ref "U5")
      (value "DS0")
      (footprint "0805D")
      (fields (field (name "COMMENT_1") "LED"))
      (libsource (lib "*") (part "LED"))
    )
    (comp (ref "U6")
      (value "DS0")
      (footprint "0805D")
      (fields (field (name "COMMENT_1") "LED"))
      (libsource (lib "*") (part "LED"))
    )
    (comp (ref "U7")
      (value "DS0")
      (footprint "0805D")
      (fields (field (name "COMMENT_1") "LED"))
      (libsource (lib "*") (part "LED"))
    )
    (comp (ref "U8")
      (value "DS0")
      (footprint "0805D")
      (fields (field (name "COMMENT_1") "LED"))
      (libsource (lib "*") (part "LED"))
    )
    (comp (ref "U9")
      (value "DS0")
      (footprint "0805D")
      (fields (field (name "COMMENT_1") "LED"))
      (libsource (lib "*") (part "LED"))
    )
    (comp (ref "U10")
      (value "DS0")
      (footprint "0805D")
      (fields (field (name "COMMENT_1") "LED"))
      (libsource (lib "*") (part "LED"))
    )
    (comp (ref "U11")
      (value "DS0")
      (footprint "0805D")
      (fields (field (name "COMMENT_1") "LED"))
      (libsource (lib "*") (part "LED"))
    )
    (comp (ref "U12")
      (value "DS0")
      (footprint "0805D")
      (fields (field (name "COMMENT_1") "LED"))
      (libsource (lib "*") (part "LED"))
    )
    (comp (ref "U13")
      (value "DS0")
      (footprint "0805D")
      (fields (field (name "COMMENT_1") "LED"))
      (libsource (lib "*") (part "LED"))
    )
    (comp (ref "U14")
      (value "DS0")
      (footprint "0805D")
      (fields (field (name "COMMENT_1") "LED"))
      (libsource (lib "*") (part "LED"))
    )
    (comp (ref "U15")
      (value "DS0")
      (footprint "0805D")
      (fields (field (name "COMMENT_1") "LED"))
      (libsource (lib "*") (part "LED"))
    )
    (comp (ref "U16")
      (value "DS0")
      (footprint "0805D")
      (fields (field (name "COMMENT_1") "LED"))
      (libsource (lib "*") (part "LED"))
    )
    (comp (ref "U17") (value "CH340") (footprint "SOP_8") (libsource (lib "*") (part "CH330")))
    (comp (ref "U18")
      (value "TPS737")
      (footprint "SOT-223-6_L6.5-W3.5-P1.27-BL")
      (libsource (lib "*") (part "TPS737"))
    )
    (comp (ref "U21")
      (value "DS0")
      (footprint "0805D")
      (fields (field (name "COMMENT_1") "LED"))
      (libsource (lib "*") (part "LED"))
    )
    (comp (ref "Y1") (value "XTAL") (footprint "XTAL3") (libsource (lib "PCB_Project1") (part "XTAL")))
    (comp (ref "Y6") (value "KEY") (footprint "KEY_3_6_2.5") (libsource (lib "*") (part "KEY")))
  )
  (nets
    (net (code "1") (name "+5V") (class "Default")
      (node (ref "C1") (pin "2") (pinfunction "2_2") (pintype "passive"))
      (node (ref "C15") (pin "2") (pinfunction "2_2") (pintype "passive"))
      (node (ref "C16") (pin "2") (pinfunction "2_2") (pintype "passive"))
      (node (ref "C43") (pin "2") (pinfunction "2_2") (pintype "passive"))
      (node (ref "C44") (pin "2") (pinfunction "2_2") (pintype "passive"))
      (node (ref "C45") (pin "2") (pinfunction "2_2") (pintype "passive"))
      (node (ref "J1") (pin "1") (pinfunction "VCC_1") (pintype "passive"))
      (node (ref "U17") (pin "5") (pinfunction "VCC_5") (pintype "passive"))
      (node (ref "U18") (pin "1") (pinfunction "IN_1") (pintype "passive"))
      (node (ref "U18") (pin "5") (pinfunction "EN_5") (pintype "passive"))
    )
    (net (code "2") (name "/ADC1") (class "Default")
      (node (ref "C20") (pin "1") (pinfunction "1_1") (pintype "passive"))
      (node (ref "R29") (pin "2") (pinfunction "2_2") (pintype "passive"))
      (node (ref "U3") (pin "10") (pinfunction "PA0/WKUP/ADC123_IN0/T2C1ETR/T5C1/T8ETR_10") (pintype "passive"))
    )
    (net (code "3") (name "/ADC2") (class "Default")
      (node (ref "R29") (pin "5") (pinfunction "5_5") (pintype "passive"))
      (node (ref "R30") (pin "2") (pinfunction "2_2") (pintype "passive"))
      (node (ref "U3") (pin "11") (pinfunction "PA1/ADC123_IN1/T5C2/T2C2_11") (pintype "passive"))
    )
    (net (code "4") (name "/ADC3") (class "Default")
      (node (ref "C21") (pin "2") (pinfunction "2_2") (pintype "passive"))
      (node (ref "R29") (pin "7") (pinfunction "7_7") (pintype "passive"))
      (node (ref "U3") (pin "12") (pinfunction "PA2/ADC123_IN2/USART2_TX/T5C3/T2C3_12") (pintype "passive"))
    )
    (net (code "5") (name "/ADC4") (class "Default")
      (node (ref "C22") (pin "1") (pinfunction "1_1") (pintype "passive"))
      (node (ref "R29") (pin "10") (pinfunction "10_10") (pintype "passive"))
      (node (ref "U3") (pin "13") (pinfunction "PA3/ADC123_IN3/USART2_RX/T5C4/T2C4_13") (pintype "passive"))
    )
    (net (code "6") (name "/ADC5") (class "Default")
      (node (ref "C23") (pin "1") (pinfunction "1_1") (pintype "passive"))
      (node (ref "R31") (pin "2") (pinfunction "2_2") (pintype "passive"))
      (node (ref "U3") (pin "14") (pinfunction "PA4/ADC123_IN4/DAC_OUT1/SPI1_NSS_14") (pintype "passive"))
    )
    (net (code "7") (name "/ADC6") (class "Default")
      (node (ref "R31") (pin "5") (pinfunction "5_5") (pintype "passive"))
      (node (ref "R32") (pin "2") (pinfunction "2_2") (pintype "passive"))
      (node (ref "U3") (pin "15") (pinfunction "PA5/ADC123_IN5/DAC_OUT2/SPI1_SCK_15") (pintype "passive"))
    )
    (net (code "8") (name "/ADC7") (class "Default")
      (node (ref "C24") (pin "2") (pinfunction "2_2") (pintype "passive"))
      (node (ref "R31") (pin "7") (pinfunction "7_7") (pintype "passive"))
      (node (ref "U3") (pin "16") (pinfunction "PA6/ADC123_IN6/SPI1_MISO/T8T1BKIN/T3C1_16") (pintype "passive"))
    )
    (net (code "9") (name "/ADC8") (class "Default")
      (node (ref "C25") (pin "1") (pinfunction "1_1") (pintype "passive"))
      (node (ref "R31") (pin "10") (pinfunction "10_10") (pintype "passive"))
      (node (ref "U3") (pin "17") (pinfunction "PA7/ADC123_IN7/SPI1_MOSI/T8C1N/T3C2/T1C1_17") (pintype "passive"))
    )
    (net (code "10") (name "/ADC9") (class "Default")
      (node (ref "C28") (pin "1") (pinfunction "1_1") (pintype "passive"))
      (node (ref "R33") (pin "2") (pinfunction "2_2") (pintype "passive"))
      (node (ref "U3") (pin "18") (pinfunction "PB0/ADC123_IN8/T3C3/T8C2N/T1C2N_18") (pintype "passive"))
    )
    (net (code "11") (name "/BOOT0") (class "Default")
      (node (ref "R40") (pin "1") (pinfunction "1_1") (pintype "passive"))
      (node (ref "R82") (pin "2") (pinfunction "2_2") (pintype "passive"))
      (node (ref "U3") (pin "44") (pinfunction "BOOT0_44") (pintype "passive"))
    )
    (net (code "12") (name "/BOOT1") (class "Default")
      (node (ref "R81") (pin "1") (pinfunction "1_1") (pintype "passive"))
      (node (ref "R83") (pin "2") (pinfunction "2_2") (pintype "passive"))
      (node (ref "U3") (pin "20") (pinfunction "PB2/BOOT1_20") (pintype "passive"))
    )
    (net (code "13") (name "/CH330_D+") (class "Default")
      (node (ref "J1") (pin "3") (pinfunction "D+_3") (pintype "passive"))
      (node (ref "U17") (pin "1") (pinfunction "UD+_1") (pintype "passive"))
    )
    (net (code "14") (name "/CH330_D-") (class "Default")
      (node (ref "J1") (pin "2") (pinfunction "D-_2") (pintype "passive"))
      (node (ref "U17") (pin "2") (pinfunction "UD-_2") (pintype "passive"))
    )
    (net (code "15") (name "/LED0") (class "Default")
      (node (ref "U14") (pin "2") (pinfunction "2_2") (pintype "passive"))
      (node (ref "U3") (pin "2") (pinfunction "PC13-TAMPER-RTC_2") (pintype "passive"))
    )
    (net (code "16") (name "/LED1") (class "Default")
      (node (ref "U15") (pin "2") (pinfunction "2_2") (pintype "passive"))
      (node (ref "U3") (pin "3") (pinfunction "PC14-OSC32_IN_3") (pintype "passive"))
    )
    (net (code "17") (name "/LED2") (class "Default")
      (node (ref "U16") (pin "2") (pinfunction "2_2") (pintype "passive"))
      (node (ref "U3") (pin "4") (pinfunction "PC15-OSC32_OUT_4") (pintype "passive"))
    )
    (net (code "18") (name "/NRST") (class "Default")
      (node (ref "C108") (pin "1") (pinfunction "1_1") (pintype "passive"))
      (node (ref "U3") (pin "7") (pinfunction "NRST_7") (pintype "passive"))
      (node (ref "Y6") (pin "1") (pinfunction "1_1") (pintype "passive"))
    )
    (net (code "19") (name "/OSCIN") (class "Default")
      (node (ref "C26") (pin "2") (pinfunction "2_2") (pintype "passive"))
      (node (ref "U3") (pin "5") (pinfunction "OSC_IN_5") (pintype "passive"))
      (node (ref "Y1") (pin "2") (pinfunction "2_2") (pintype "passive"))
    )
    (net (code "20") (name "/OSCOUT") (class "Default")
      (node (ref "C27") (pin "2") (pinfunction "2_2") (pintype "passive"))
      (node (ref "U3") (pin "6") (pinfunction "OSC_OUT_6") (pintype "passive"))
      (node (ref "Y1") (pin "1") (pinfunction "1_1") (pintype "passive"))
    )
    (net (code "21") (name "/PA11") (class "Default")
      (node (ref "P1") (pin "4") (pinfunction "4_4") (pintype "passive"))
      (node (ref "U3") (pin "32") (pinfunction "PA11/CAN_RX/T1C4/USBDM_32") (pintype "passive"))
    )
    (net (code "22") (name "/PA12") (class "Default")
      (node (ref "P1") (pin "3") (pinfunction "3_3") (pintype "passive"))
      (node (ref "U3") (pin "33") (pinfunction "PA12/CAN_TX/T1ETR/USBDP_33") (pintype "passive"))
    )
    (net (code "23") (name "/PB3") (class "Default")
      (node (ref "C3") (pin "1") (pinfunction "1_1") (pintype "passive"))
      (node (ref "R1") (pin "2") (pinfunction "2_2") (pintype "passive"))
      (node (ref "R2") (pin "2") (pinfunction "2_2") (pintype "passive"))
      (node (ref "S1") (pin "2") (pinfunction "2_2") (pintype "passive"))
      (node (ref "U3") (pin "39") (pinfunction "PB3/JTDO/SPI3_SCK/I2S3_CK/T2C2/SPI1_SCK_39") (pintype "passive"))
    )
    (net (code "24") (name "/PB4") (class "Default")
      (node (ref "C4") (pin "1") (pinfunction "1_1") (pintype "passive"))
      (node (ref "R3") (pin "2") (pinfunction "2_2") (pintype "passive"))
      (node (ref "R4") (pin "2") (pinfunction "2_2") (pintype "passive"))
      (node (ref "S2") (pin "2") (pinfunction "2_2") (pintype "passive"))
      (node (ref "U3") (pin "40") (pinfunction "PB4/NJTRST/SPI3_MISO/T3C1/SPI1_MISO_40") (pintype "passive"))
    )
    (net (code "25") (name "/PB5") (class "Default")
      (node (ref "C5") (pin "1") (pinfunction "1_1") (pintype "passive"))
      (node (ref "R5") (pin "2") (pinfunction "2_2") (pintype "passive"))
      (node (ref "R6") (pin "2") (pinfunction "2_2") (pintype "passive"))
      (node (ref "S3") (pin "2") (pinfunction "2_2") (pintype "passive"))
      (node (ref "U3") (pin "41") (pinfunction "PB5/I2C1_SMBA/I2S3_SD/SPI3_MOSI/T3C2/SPI_41") (pintype "passive"))
    )
    (net (code "26") (name "/PB6") (class "Default")
      (node (ref "C6") (pin "1") (pinfunction "1_1") (pintype "passive"))
      (node (ref "R7") (pin "2") (pinfunction "2_2") (pintype "passive"))
      (node (ref "R8") (pin "2") (pinfunction "2_2") (pintype "passive"))
      (node (ref "S4") (pin "2") (pinfunction "2_2") (pintype "passive"))
      (node (ref "U3") (pin "42") (pinfunction "PB6/I2C1_SCL/T4C1/USART1_TX_42") (pintype "passive"))
    )
    (net (code "27") (name "/PB7") (class "Default")
      (node (ref "C7") (pin "1") (pinfunction "1_1") (pintype "passive"))
      (node (ref "R10") (pin "2") (pinfunction "2_2") (pintype "passive"))
      (node (ref "R9") (pin "2") (pinfunction "2_2") (pintype "passive"))
      (node (ref "S5") (pin "2") (pinfunction "2_2") (pintype "passive"))
      (node (ref "U3") (pin "43") (pinfunction "PB7/I2C1_SDA/FSMC_NADV/USART1_RX_43") (pintype "passive"))
    )
    (net (code "28") (name "/PB8") (class "Default")
      (node (ref "C8") (pin "1") (pinfunction "1_1") (pintype "passive"))
      (node (ref "R11") (pin "2") (pinfunction "2_2") (pintype "passive"))
      (node (ref "R12") (pin "2") (pinfunction "2_2") (pintype "passive"))
      (node (ref "S6") (pin "2") (pinfunction "2_2") (pintype "passive"))
      (node (ref "U3") (pin "45") (pinfunction "PB8/SDIO_D4/I2C1_SCL/T4C3(7)/CAN_RX_45") (pintype "passive"))
    )
    (net (code "29") (name "/PB9") (class "Default")
      (node (ref "C9") (pin "1") (pinfunction "1_1") (pintype "passive"))
      (node (ref "R13") (pin "2") (pinfunction "2_2") (pintype "passive"))
      (node (ref "R14") (pin "2") (pinfunction "2_2") (pintype "passive"))
      (node (ref "S7") (pin "2") (pinfunction "2_2") (pintype "passive"))
      (node (ref "U3") (pin "46") (pinfunction "PB9/SDIO_D5/I2C1_SDA/T4C4/CAN_TX_46") (pintype "passive"))
    )
    (net (code "30") (name "/PB10") (class "Default")
      (node (ref "C10") (pin "1") (pinfunction "1_1") (pintype "passive"))
      (node (ref "R15") (pin "2") (pinfunction "2_2") (pintype "passive"))
      (node (ref "R16") (pin "2") (pinfunction "2_2") (pintype "passive"))
      (node (ref "S8") (pin "2") (pinfunction "2_2") (pintype "passive"))
      (node (ref "U3") (pin "21") (pinfunction "PB10/USART3_TX/I2C2_SCL/T2C3_21") (pintype "passive"))
    )
    (net (code "31") (name "/PB11") (class "Default")
      (node (ref "C11") (pin "1") (pinfunction "1_1") (pintype "passive"))
      (node (ref "R17") (pin "2") (pinfunction "2_2") (pintype "passive"))
      (node (ref "R18") (pin "2") (pinfunction "2_2") (pintype "passive"))
      (node (ref "S9") (pin "2") (pinfunction "2_2") (pintype "passive"))
      (node (ref "U3") (pin "22") (pinfunction "PB11/USART3_RX/I2C2_SDA/T2C4_22") (pintype "passive"))
    )
    (net (code "32") (name "/PB12") (class "Default")
      (node (ref "C12") (pin "1") (pinfunction "1_1") (pintype "passive"))
      (node (ref "R19") (pin "2") (pinfunction "2_2") (pintype "passive"))
      (node (ref "R20") (pin "2") (pinfunction "2_2") (pintype "passive"))
      (node (ref "S10") (pin "2") (pinfunction "2_2") (pintype "passive"))
      (node (ref "U3") (pin "25") (pinfunction "PB12/I2S2_WS/T1BKIN/SPI2_NSS/I2C2_SMBA_25") (pintype "passive"))
    )
    (net (code "33") (name "/PB13") (class "Default")
      (node (ref "C13") (pin "1") (pinfunction "1_1") (pintype "passive"))
      (node (ref "R21") (pin "2") (pinfunction "2_2") (pintype "passive"))
      (node (ref "R22") (pin "2") (pinfunction "2_2") (pintype "passive"))
      (node (ref "S11") (pin "2") (pinfunction "2_2") (pintype "passive"))
      (node (ref "U3") (pin "26") (pinfunction "PB13/I2S2_CK/T1CH1N/SPI2_SCK_26") (pintype "passive"))
    )
    (net (code "34") (name "/PB14") (class "Default")
      (node (ref "C14") (pin "1") (pinfunction "1_1") (pintype "passive"))
      (node (ref "R23") (pin "2") (pinfunction "2_2") (pintype "passive"))
      (node (ref "R24") (pin "2") (pinfunction "2_2") (pintype "passive"))
      (node (ref "S12") (pin "2") (pinfunction "2_2") (pintype "passive"))
      (node (ref "U3") (pin "27") (pinfunction "PB14/T1CH2N/SPI2_MISO_27") (pintype "passive"))
    )
    (net (code "35") (name "/SWCLK") (class "Default")
      (node (ref "P4") (pin "2") (pinfunction "2_2") (pintype "passive"))
      (node (ref "U3") (pin "37") (pinfunction "PA14/JTCK/SWCLK_37") (pintype "passive"))
    )
    (net (code "36") (name "/SWIO") (class "Default")
      (node (ref "P4") (pin "3") (pinfunction "3_3") (pintype "passive"))
      (node (ref "U3") (pin "34") (pinfunction "PA13/JTMS/SWDIO_34") (pintype "passive"))
    )
    (net (code "37") (name "/U1_RX") (class "Default")
      (node (ref "P2") (pin "2") (pinfunction "2_2") (pintype "passive"))
      (node (ref "U17") (pin "6") (pinfunction "TXD_6") (pintype "passive"))
      (node (ref "U3") (pin "31") (pinfunction "PA10/T1C3/USART1_RX_31") (pintype "passive"))
    )
    (net (code "38") (name "/U1_TX") (class "Default")
      (node (ref "P2") (pin "3") (pinfunction "3_3") (pintype "passive"))
      (node (ref "U17") (pin "7") (pinfunction "RXD_7") (pintype "passive"))
      (node (ref "U3") (pin "30") (pinfunction "PA9/T1C2/USART1_TX_30") (pintype "passive"))
    )
    (net (code "39") (name "AGND") (class "Default")
      (node (ref "C1") (pin "1") (pinfunction "1_1") (pintype "passive"))
      (node (ref "C10") (pin "2") (pinfunction "2_2") (pintype "passive"))
      (node (ref "C102") (pin "2") (pinfunction "2_2") (pintype "passive"))
      (node (ref "C103") (pin "2") (pinfunction "2_2") (pintype "passive"))
      (node (ref "C104") (pin "2") (pinfunction "2_2") (pintype "passive"))
      (node (ref "C108") (pin "2") (pinfunction "2_2") (pintype "passive"))
      (node (ref "C11") (pin "2") (pinfunction "2_2") (pintype "passive"))
      (node (ref "C12") (pin "2") (pinfunction "2_2") (pintype "passive"))
      (node (ref "C13") (pin "2") (pinfunction "2_2") (pintype "passive"))
      (node (ref "C14") (pin "2") (pinfunction "2_2") (pintype "passive"))
      (node (ref "C15") (pin "1") (pinfunction "1_1") (pintype "passive"))
      (node (ref "C16") (pin "1") (pinfunction "1_1") (pintype "passive"))
      (node (ref "C17") (pin "2") (pinfunction "2_2") (pintype "passive"))
      (node (ref "C18") (pin "1") (pinfunction "1_1") (pintype "passive"))
      (node (ref "C19") (pin "1") (pinfunction "1_1") (pintype "passive"))
      (node (ref "C2") (pin "1") (pinfunction "1_1") (pintype "passive"))
      (node (ref "C20") (pin "2") (pinfunction "2_2") (pintype "passive"))
      (node (ref "C22") (pin "2") (pinfunction "2_2") (pintype "passive"))
      (node (ref "C23") (pin "2") (pinfunction "2_2") (pintype "passive"))
      (node (ref "C25") (pin "2") (pinfunction "2_2") (pintype "passive"))
      (node (ref "C26") (pin "1") (pinfunction "1_1") (pintype "passive"))
      (node (ref "C27") (pin "1") (pinfunction "1_1") (pintype "passive"))
      (node (ref "C28") (pin "2") (pinfunction "2_2") (pintype "passive"))
      (node (ref "C3") (pin "2") (pinfunction "2_2") (pintype "passive"))
      (node (ref "C30") (pin "1") (pinfunction "1_1") (pintype "passive"))
      (node (ref "C4") (pin "2") (pinfunction "2_2") (pintype "passive"))
      (node (ref "C43") (pin "1") (pinfunction "1_1") (pintype "passive"))
      (node (ref "C44") (pin "1") (pinfunction "1_1") (pintype "passive"))
      (node (ref "C45") (pin "1") (pinfunction "1_1") (pintype "passive"))
      (node (ref "C46") (pin "1") (pinfunction "1_1") (pintype "passive"))
      (node (ref "C47") (pin "1") (pinfunction "1_1") (pintype "passive"))
      (node (ref "C48") (pin "1") (pinfunction "1_1") (pintype "passive"))
      (node (ref "C49") (pin "1") (pinfunction "1_1") (pintype "passive"))
      (node (ref "C5") (pin "2") (pinfunction "2_2") (pintype "passive"))
      (node (ref "C6") (pin "2") (pinfunction "2_2") (pintype "passive"))
      (node (ref "C66") (pin "2") (pinfunction "2_2") (pintype "passive"))
      (node (ref "C67") (pin "2") (pinfunction "2_2") (pintype "passive"))
      (node (ref "C68") (pin "2") (pinfunction "2_2") (pintype "passive"))
      (node (ref "C69") (pin "2") (pinfunction "2_2") (pintype "passive"))
      (node (ref "C7") (pin "2") (pinfunction "2_2") (pintype "passive"))
      (node (ref "C70") (pin "2") (pinfunction "2_2") (pintype "passive"))
      (node (ref "C71") (pin "2") (pinfunction "2_2") (pintype "passive"))
      (node (ref "C72") (pin "2") (pinfunction "2_2") (pintype "passive"))
      (node (ref "C73") (pin "2") (pinfunction "2_2") (pintype "passive"))
      (node (ref "C8") (pin "2") (pinfunction "2_2") (pintype "passive"))
      (node (ref "C9") (pin "2") (pinfunction "2_2") (pintype "passive"))
      (node (ref "J1") (pin "5") (pinfunction "GND_5") (pintype "passive"))
      (node (ref "P1") (pin "1") (pinfunction "1_1") (pintype "passive"))
      (node (ref "P2") (pin "1") (pinfunction "1_1") (pintype "passive"))
      (node (ref "P4") (pin "1") (pinfunction "1_1") (pintype "passive"))
      (node (ref "R10") (pin "1") (pinfunction "1_1") (pintype "passive"))
      (node (ref "R12") (pin "1") (pinfunction "1_1") (pintype "passive"))
      (node (ref "R14") (pin "1") (pinfunction "1_1") (pintype "passive"))
      (node (ref "R16") (pin "1") (pinfunction "1_1") (pintype "passive"))
      (node (ref "R18") (pin "1") (pinfunction "1_1") (pintype "passive"))
      (node (ref "R2") (pin "1") (pinfunction "1_1") (pintype "passive"))
      (node (ref "R20") (pin "1") (pinfunction "1_1") (pintype "passive"))
      (node (ref "R22") (pin "1") (pinfunction "1_1") (pintype "passive"))
      (node (ref "R24") (pin "1") (pinfunction "1_1") (pintype "passive"))
      (node (ref "R29") (pin "11") (pinfunction "11_11") (pintype "passive"))
      (node (ref "R29") (pin "3") (pinfunction "3_3") (pintype "passive"))
      (node (ref "R29") (pin "6") (pinfunction "6_6") (pintype "passive"))
      (node (ref "R30") (pin "1") (pinfunction "1_1") (pintype "passive"))
      (node (ref "R31") (pin "11") (pinfunction "11_11") (pintype "passive"))
      (node (ref "R31") (pin "3") (pinfunction "3_3") (pintype "passive"))
      (node (ref "R31") (pin "6") (pinfunction "6_6") (pintype "passive"))
      (node (ref "R32") (pin "1") (pinfunction "1_1") (pintype "passive"))
      (node (ref "R33") (pin "3") (pinfunction "3_3") (pintype "passive"))
      (node (ref "R4") (pin "1") (pinfunction "1_1") (pintype "passive"))
      (node (ref "R6") (pin "1") (pinfunction "1_1") (pintype "passive"))
      (node (ref "R8") (pin "1") (pinfunction "1_1") (pintype "passive"))
      (node (ref "R82") (pin "1") (pinfunction "1_1") (pintype "passive"))
      (node (ref "R83") (pin "1") (pinfunction "1_1") (pintype "passive"))
      (node (ref "R88") (pin "2") (pinfunction "2_2") (pintype "passive"))
      (node (ref "U1") (pin "2") (pinfunction "2_2") (pintype "passive"))
      (node (ref "U10") (pin "2") (pinfunction "2_2") (pintype "passive"))
      (node (ref "U11") (pin "2") (pinfunction "2_2") (pintype "passive"))
      (node (ref "U12") (pin "2") (pinfunction "2_2") (pintype "passive"))
      (node (ref "U13") (pin "2") (pinfunction "2_2") (pintype "passive"))
      (node (ref "U17") (pin "3") (pinfunction "GND_3") (pintype "passive"))
      (node (ref "U18") (pin "3") (pinfunction "GND_3") (pintype "passive"))
      (node (ref "U18") (pin "6") (pinfunction "GND_6") (pintype "passive"))
      (node (ref "U2") (pin "2") (pinfunction "2_2") (pintype "passive"))
      (node (ref "U21") (pin "2") (pinfunction "2_2") (pintype "passive"))
      (node (ref "U3") (pin "23") (pinfunction "VSS_1_23") (pintype "passive"))
      (node (ref "U3") (pin "35") (pinfunction "VSS_2_35") (pintype "passive"))
      (node (ref "U3") (pin "47") (pinfunction "VSS_3_47") (pintype "passive"))
      (node (ref "U3") (pin "8") (pinfunction "VSSA_8") (pintype "passive"))
      (node (ref "U4") (pin "2") (pinfunction "2_2") (pintype "passive"))
      (node (ref "U5") (pin "2") (pinfunction "2_2") (pintype "passive"))
      (node (ref "U6") (pin "2") (pinfunction "2_2") (pintype "passive"))
      (node (ref "U7") (pin "2") (pinfunction "2_2") (pintype "passive"))
      (node (ref "U8") (pin "2") (pinfunction "2_2") (pintype "passive"))
      (node (ref "U9") (pin "2") (pinfunction "2_2") (pintype "passive"))
      (node (ref "Y1") (pin "3") (pinfunction "3_3") (pintype "passive"))
      (node (ref "Y1") (pin "4") (pinfunction "4_4") (pintype "passive"))
      (node (ref "Y6") (pin "2") (pinfunction "2_2") (pintype "passive"))
    )
    (net (code "40") (name "Net-(R1-Pad1)") (class "Default")
      (node (ref "R1") (pin "1") (pinfunction "1_1") (pintype "passive"))
      (node (ref "U21") (pin "1") (pinfunction "1_1") (pintype "passive"))
    )
    (net (code "41") (name "Net-(R3-Pad1)") (class "Default")
      (node (ref "R3") (pin "1") (pinfunction "1_1") (pintype "passive"))
      (node (ref "U1") (pin "1") (pinfunction "1_1") (pintype "passive"))
    )
    (net (code "42") (name "Net-(R5-Pad1)") (class "Default")
      (node (ref "R5") (pin "1") (pinfunction "1_1") (pintype "passive"))
      (node (ref "U2") (pin "1") (pinfunction "1_1") (pintype "passive"))
    )
    (net (code "43") (name "Net-(R7-Pad1)") (class "Default")
      (node (ref "R7") (pin "1") (pinfunction "1_1") (pintype "passive"))
      (node (ref "U4") (pin "1") (pinfunction "1_1") (pintype "passive"))
    )
    (net (code "44") (name "Net-(R9-Pad1)") (class "Default")
      (node (ref "R9") (pin "1") (pinfunction "1_1") (pintype "passive"))
      (node (ref "U5") (pin "1") (pinfunction "1_1") (pintype "passive"))
    )
    (net (code "45") (name "Net-(R11-Pad1)") (class "Default")
      (node (ref "R11") (pin "1") (pinfunction "1_1") (pintype "passive"))
      (node (ref "U6") (pin "1") (pinfunction "1_1") (pintype "passive"))
    )
    (net (code "46") (name "Net-(R13-Pad1)") (class "Default")
      (node (ref "R13") (pin "1") (pinfunction "1_1") (pintype "passive"))
      (node (ref "U7") (pin "1") (pinfunction "1_1") (pintype "passive"))
    )
    (net (code "47") (name "Net-(R15-Pad1)") (class "Default")
      (node (ref "R15") (pin "1") (pinfunction "1_1") (pintype "passive"))
      (node (ref "U8") (pin "1") (pinfunction "1_1") (pintype "passive"))
    )
    (net (code "48") (name "Net-(R17-Pad1)") (class "Default")
      (node (ref "R17") (pin "1") (pinfunction "1_1") (pintype "passive"))
      (node (ref "U9") (pin "1") (pinfunction "1_1") (pintype "passive"))
    )
    (net (code "49") (name "Net-(R19-Pad1)") (class "Default")
      (node (ref "R19") (pin "1") (pinfunction "1_1") (pintype "passive"))
      (node (ref "U10") (pin "1") (pinfunction "1_1") (pintype "passive"))
    )
    (net (code "50") (name "Net-(R21-Pad1)") (class "Default")
      (node (ref "R21") (pin "1") (pinfunction "1_1") (pintype "passive"))
      (node (ref "U11") (pin "1") (pinfunction "1_1") (pintype "passive"))
    )
    (net (code "51") (name "Net-(R23-Pad1)") (class "Default")
      (node (ref "R23") (pin "1") (pinfunction "1_1") (pintype "passive"))
      (node (ref "U12") (pin "1") (pinfunction "1_1") (pintype "passive"))
    )
    (net (code "52") (name "Net-(R25-Pad2)") (class "Default")
      (node (ref "R25") (pin "2") (pinfunction "2_2") (pintype "passive"))
      (node (ref "U13") (pin "1") (pinfunction "1_1") (pintype "passive"))
    )
    (net (code "53") (name "Net-(R26-Pad2)") (class "Default")
      (node (ref "R26") (pin "2") (pinfunction "2_2") (pintype "passive"))
      (node (ref "U14") (pin "1") (pinfunction "1_1") (pintype "passive"))
    )
    (net (code "54") (name "Net-(R27-Pad2)") (class "Default")
      (node (ref "R27") (pin "2") (pinfunction "2_2") (pintype "passive"))
      (node (ref "U15") (pin "1") (pinfunction "1_1") (pintype "passive"))
    )
    (net (code "55") (name "Net-(R28-Pad2)") (class "Default")
      (node (ref "R28") (pin "2") (pinfunction "2_2") (pintype "passive"))
      (node (ref "U16") (pin "1") (pinfunction "1_1") (pintype "passive"))
    )
    (net (code "56") (name "Net-(U17-V3)") (class "Default")
      (node (ref "C17") (pin "1") (pinfunction "1_1") (pintype "passive"))
      (node (ref "U17") (pin "8") (pinfunction "V3_8") (pintype "passive"))
    )
    (net (code "57") (name "Net-(U18-FB)") (class "Default")
      (node (ref "R51") (pin "2") (pinfunction "2_2") (pintype "passive"))
      (node (ref "R88") (pin "1") (pinfunction "1_1") (pintype "passive"))
      (node (ref "U18") (pin "4") (pinfunction "FB_4") (pintype "passive"))
    )
    (net (code "58") (name "VCC_3.3V") (class "Default")
      (node (ref "C102") (pin "1") (pinfunction "1_1") (pintype "passive"))
      (node (ref "C103") (pin "1") (pinfunction "1_1") (pintype "passive"))
      (node (ref "C104") (pin "1") (pinfunction "1_1") (pintype "passive"))
      (node (ref "C18") (pin "2") (pinfunction "2_2") (pintype "passive"))
      (node (ref "C19") (pin "2") (pinfunction "2_2") (pintype "passive"))
      (node (ref "C2") (pin "2") (pinfunction "2_2") (pintype "passive"))
      (node (ref "C21") (pin "1") (pinfunction "1_1") (pintype "passive"))
      (node (ref "C24") (pin "1") (pinfunction "1_1") (pintype "passive"))
      (node (ref "C30") (pin "2") (pinfunction "2_2") (pintype "passive"))
      (node (ref "C46") (pin "2") (pinfunction "2_2") (pintype "passive"))
      (node (ref "C47") (pin "2") (pinfunction "2_2") (pintype "passive"))
      (node (ref "C48") (pin "2") (pinfunction "2_2") (pintype "passive"))
      (node (ref "C49") (pin "2") (pinfunction "2_2") (pintype "passive"))
      (node (ref "C66") (pin "1") (pinfunction "1_1") (pintype "passive"))
      (node (ref "C67") (pin "1") (pinfunction "1_1") (pintype "passive"))
      (node (ref "C68") (pin "1") (pinfunction "1_1") (pintype "passive"))
      (node (ref "C69") (pin "1") (pinfunction "1_1") (pintype "passive"))
      (node (ref "C70") (pin "1") (pinfunction "1_1") (pintype "passive"))
      (node (ref "C71") (pin "1") (pinfunction "1_1") (pintype "passive"))
      (node (ref "C72") (pin "1") (pinfunction "1_1") (pintype "passive"))
      (node (ref "C73") (pin "1") (pinfunction "1_1") (pintype "passive"))
      (node (ref "P1") (pin "2") (pinfunction "2_2") (pintype "passive"))
      (node (ref "P2") (pin "4") (pinfunction "4_4") (pintype "passive"))
      (node (ref "P4") (pin "4") (pinfunction "4_4") (pintype "passive"))
      (node (ref "R25") (pin "1") (pinfunction "1_1") (pintype "passive"))
      (node (ref "R26") (pin "1") (pinfunction "1_1") (pintype "passive"))
      (node (ref "R27") (pin "1") (pinfunction "1_1") (pintype "passive"))
      (node (ref "R28") (pin "1") (pinfunction "1_1") (pintype "passive"))
      (node (ref "R29") (pin "1") (pinfunction "1_1") (pintype "passive"))
      (node (ref "R29") (pin "4") (pinfunction "4_4") (pintype "passive"))
      (node (ref "R29") (pin "8") (pinfunction "8_8") (pintype "passive"))
      (node (ref "R29") (pin "9") (pinfunction "9_9") (pintype "passive"))
      (node (ref "R31") (pin "1") (pinfunction "1_1") (pintype "passive"))
      (node (ref "R31") (pin "4") (pinfunction "4_4") (pintype "passive"))
      (node (ref "R31") (pin "8") (pinfunction "8_8") (pintype "passive"))
      (node (ref "R31") (pin "9") (pinfunction "9_9") (pintype "passive"))
      (node (ref "R33") (pin "1") (pinfunction "1_1") (pintype "passive"))
      (node (ref "R40") (pin "2") (pinfunction "2_2") (pintype "passive"))
      (node (ref "R51") (pin "1") (pinfunction "1_1") (pintype "passive"))
      (node (ref "R81") (pin "2") (pinfunction "2_2") (pintype "passive"))
      (node (ref "S1") (pin "3") (pinfunction "3_3") (pintype "passive"))
      (node (ref "S10") (pin "3") (pinfunction "3_3") (pintype "passive"))
      (node (ref "S11") (pin "3") (pinfunction "3_3") (pintype "passive"))
      (node (ref "S12") (pin "3") (pinfunction "3_3") (pintype "passive"))
      (node (ref "S2") (pin "3") (pinfunction "3_3") (pintype "passive"))
      (node (ref "S3") (pin "3") (pinfunction "3_3") (pintype "passive"))
      (node (ref "S4") (pin "3") (pinfunction "3_3") (pintype "passive"))
      (node (ref "S5") (pin "3") (pinfunction "3_3") (pintype "passive"))
      (node (ref "S6") (pin "3") (pinfunction "3_3") (pintype "passive"))
      (node (ref "S7") (pin "3") (pinfunction "3_3") (pintype "passive"))
      (node (ref "S8") (pin "3") (pinfunction "3_3") (pintype "passive"))
      (node (ref "S9") (pin "3") (pinfunction "3_3") (pintype "passive"))
      (node (ref "U18") (pin "2") (pinfunction "OUT_2") (pintype "passive"))
      (node (ref "U3") (pin "24") (pinfunction "VDD_1_24") (pintype "passive"))
      (node (ref "U3") (pin "36") (pinfunction "VDD_2_36") (pintype "passive"))
      (node (ref "U3") (pin "48") (pinfunction "VDD_3_48") (pintype "passive"))
      (node (ref "U3") (pin "9") (pinfunction "VDDA_9") (pintype "passive"))
    )
    (net (code "59") (name "unconnected-(J1-EP-Pad6)") (class "Default")
      (node (ref "J1") (pin "6") (pinfunction "EP_6") (pintype "passive"))
    )
    (net (code "60") (name "unconnected-(J1-EP-Pad7)") (class "Default")
      (node (ref "J1") (pin "7") (pinfunction "EP_7") (pintype "passive"))
    )
    (net (code "61") (name "unconnected-(J1-ID-Pad4)") (class "Default")
      (node (ref "J1") (pin "4") (pinfunction "ID_4") (pintype "passive+no_connect"))
    )
    (net (code "62") (name "unconnected-(R33-Pad4)") (class "Default")
      (node (ref "R33") (pin "4") (pinfunction "4_4") (pintype "passive+no_connect"))
    )
    (net (code "63") (name "unconnected-(R33-Pad5)") (class "Default")
      (node (ref "R33") (pin "5") (pinfunction "5_5") (pintype "passive+no_connect"))
    )
    (net (code "64") (name "unconnected-(S1-Pad1)") (class "Default")
      (node (ref "S1") (pin "1") (pinfunction "1_1") (pintype "passive+no_connect"))
    )
    (net (code "65") (name "unconnected-(S2-Pad1)") (class "Default")
      (node (ref "S2") (pin "1") (pinfunction "1_1") (pintype "passive+no_connect"))
    )
    (net (code "66") (name "unconnected-(S3-Pad1)") (class "Default")
      (node (ref "S3") (pin "1") (pinfunction "1_1") (pintype "passive+no_connect"))
    )
    (net (code "67") (name "unconnected-(S4-Pad1)") (class "Default")
      (node (ref "S4") (pin "1") (pinfunction "1_1") (pintype "passive+no_connect"))
    )
    (net (code "68") (name "unconnected-(S5-Pad1)") (class "Default")
      (node (ref "S5") (pin "1") (pinfunction "1_1") (pintype "passive+no_connect"))
    )
    (net (code "69") (name "unconnected-(S6-Pad1)") (class "Default")
      (node (ref "S6") (pin "1") (pinfunction "1_1") (pintype "passive+no_connect"))
    )
    (net (code "70") (name "unconnected-(S7-Pad1)") (class "Default")
      (node (ref "S7") (pin "1") (pinfunction "1_1") (pintype "passive+no_connect"))
    )
    (net (code "71") (name "unconnected-(S8-Pad1)") (class "Default")
      (node (ref "S8") (pin "1") (pinfunction "1_1") (pintype "passive+no_connect"))
    )
    (net (code "72") (name "unconnected-(S9-Pad1)") (class "Default")
      (node (ref "S9") (pin "1") (pinfunction "1_1") (pintype "passive+no_connect"))
    )
    (net (code "73") (name "unconnected-(S10-Pad1)") (class "Default")
      (node (ref "S10") (pin "1") (pinfunction "1_1") (pintype "passive+no_connect"))
    )
    (net (code "74") (name "unconnected-(S11-Pad1)") (class "Default")
      (node (ref "S11") (pin "1") (pinfunction "1_1") (pintype "passive+no_connect"))
    )
    (net (code "75") (name "unconnected-(S12-Pad1)") (class "Default")
      (node (ref "S12") (pin "1") (pinfunction "1_1") (pintype "passive+no_connect"))
    )
    (net (code "76") (name "unconnected-(U3-PA8{slash}T1C1{slash}MCO-Pad29)") (class "Default")
      (node (ref "U3") (pin "29") (pinfunction "PA8/T1C1/MCO_29") (pintype "passive"))
    )
    (net (code "77") (name "unconnected-(U3-PA15{slash}JTDI{slash}I2S3_WS{slash}JTDI{slash}T2C1ETR{slash}SPI3_NSS-Pad38)") (class "Default")
      (node (ref "U3") (pin "38") (pinfunction "PA15/JTDI/I2S3_WS/JTDI/T2C1ETR/SPI3_NSS_38") (pintype "passive"))
    )
    (net (code "78") (name "unconnected-(U3-PB1{slash}ADC123_IN9{slash}T3C4{slash}T8C3N{slash}T1C3N-Pad19)") (class "Default")
      (node (ref "U3") (pin "19") (pinfunction "PB1/ADC123_IN9/T3C4/T8C3N/T1C3N_19") (pintype "passive+no_connect"))
    )
    (net (code "79") (name "unconnected-(U3-PB15{slash}I2S2_SD{slash}T1CH3N{slash}SPI2_MOSI-Pad28)") (class "Default")
      (node (ref "U3") (pin "28") (pinfunction "PB15/I2S2_SD/T1CH3N/SPI2_MOSI_28") (pintype "passive"))
    )
    (net (code "80") (name "unconnected-(U3-VBAT-Pad1)") (class "Default")
      (node (ref "U3") (pin "1") (pinfunction "VBAT_1") (pintype "passive"))
    )
    (net (code "81") (name "unconnected-(U17-RTS-Pad4)") (class "Default")
      (node (ref "U17") (pin "4") (pinfunction "RTS_4") (pintype "passive"))
    )
  )
)
